# PCB_-_BOARD.net
KiCad netlist of a schematic drawn in EAGLE
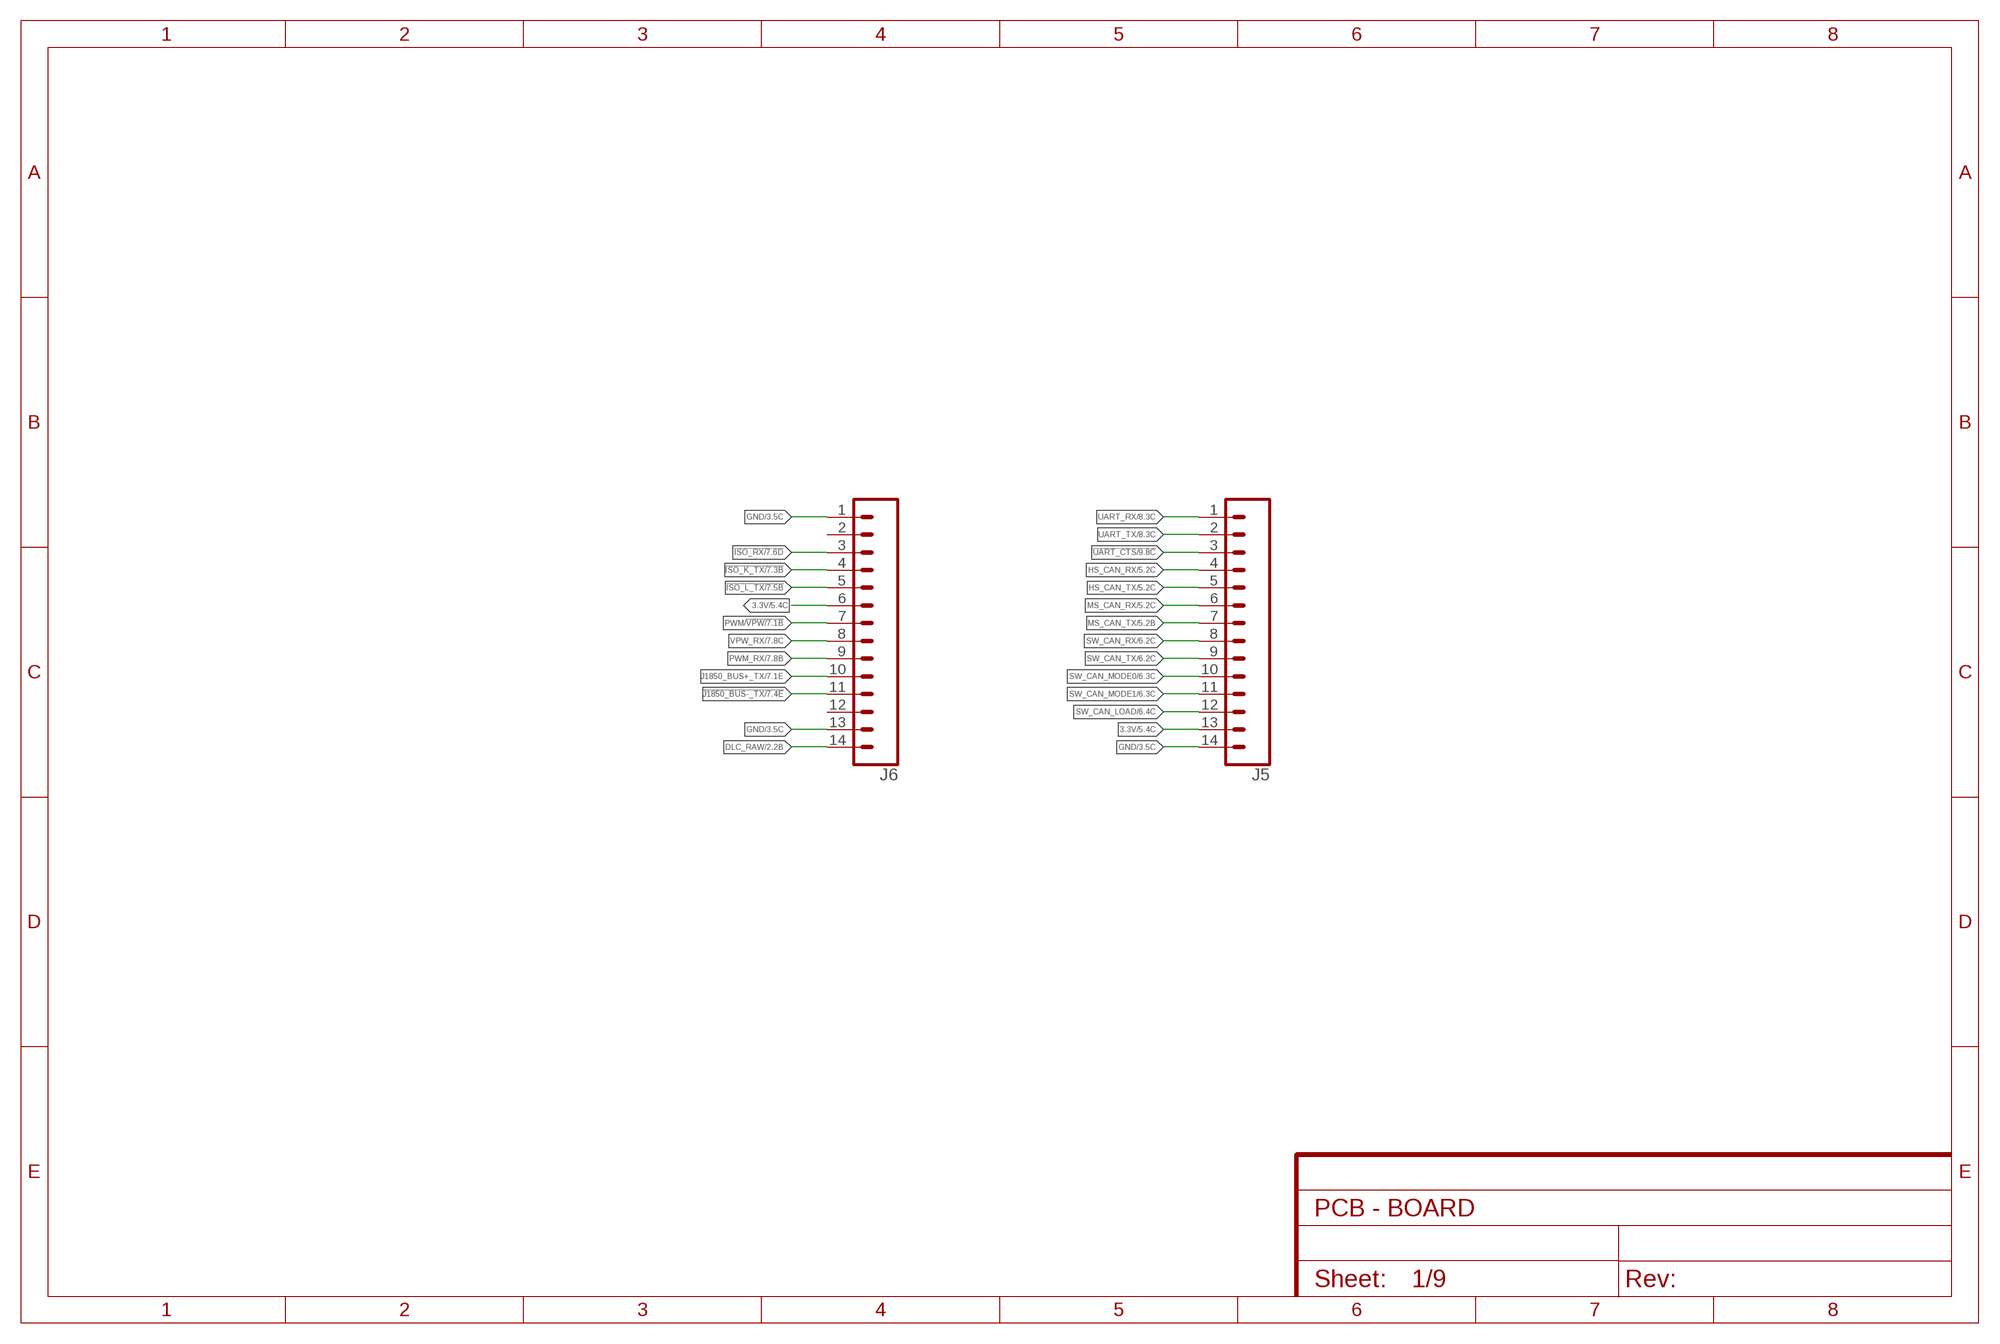
[diagram p0: schematic, sheet 1]
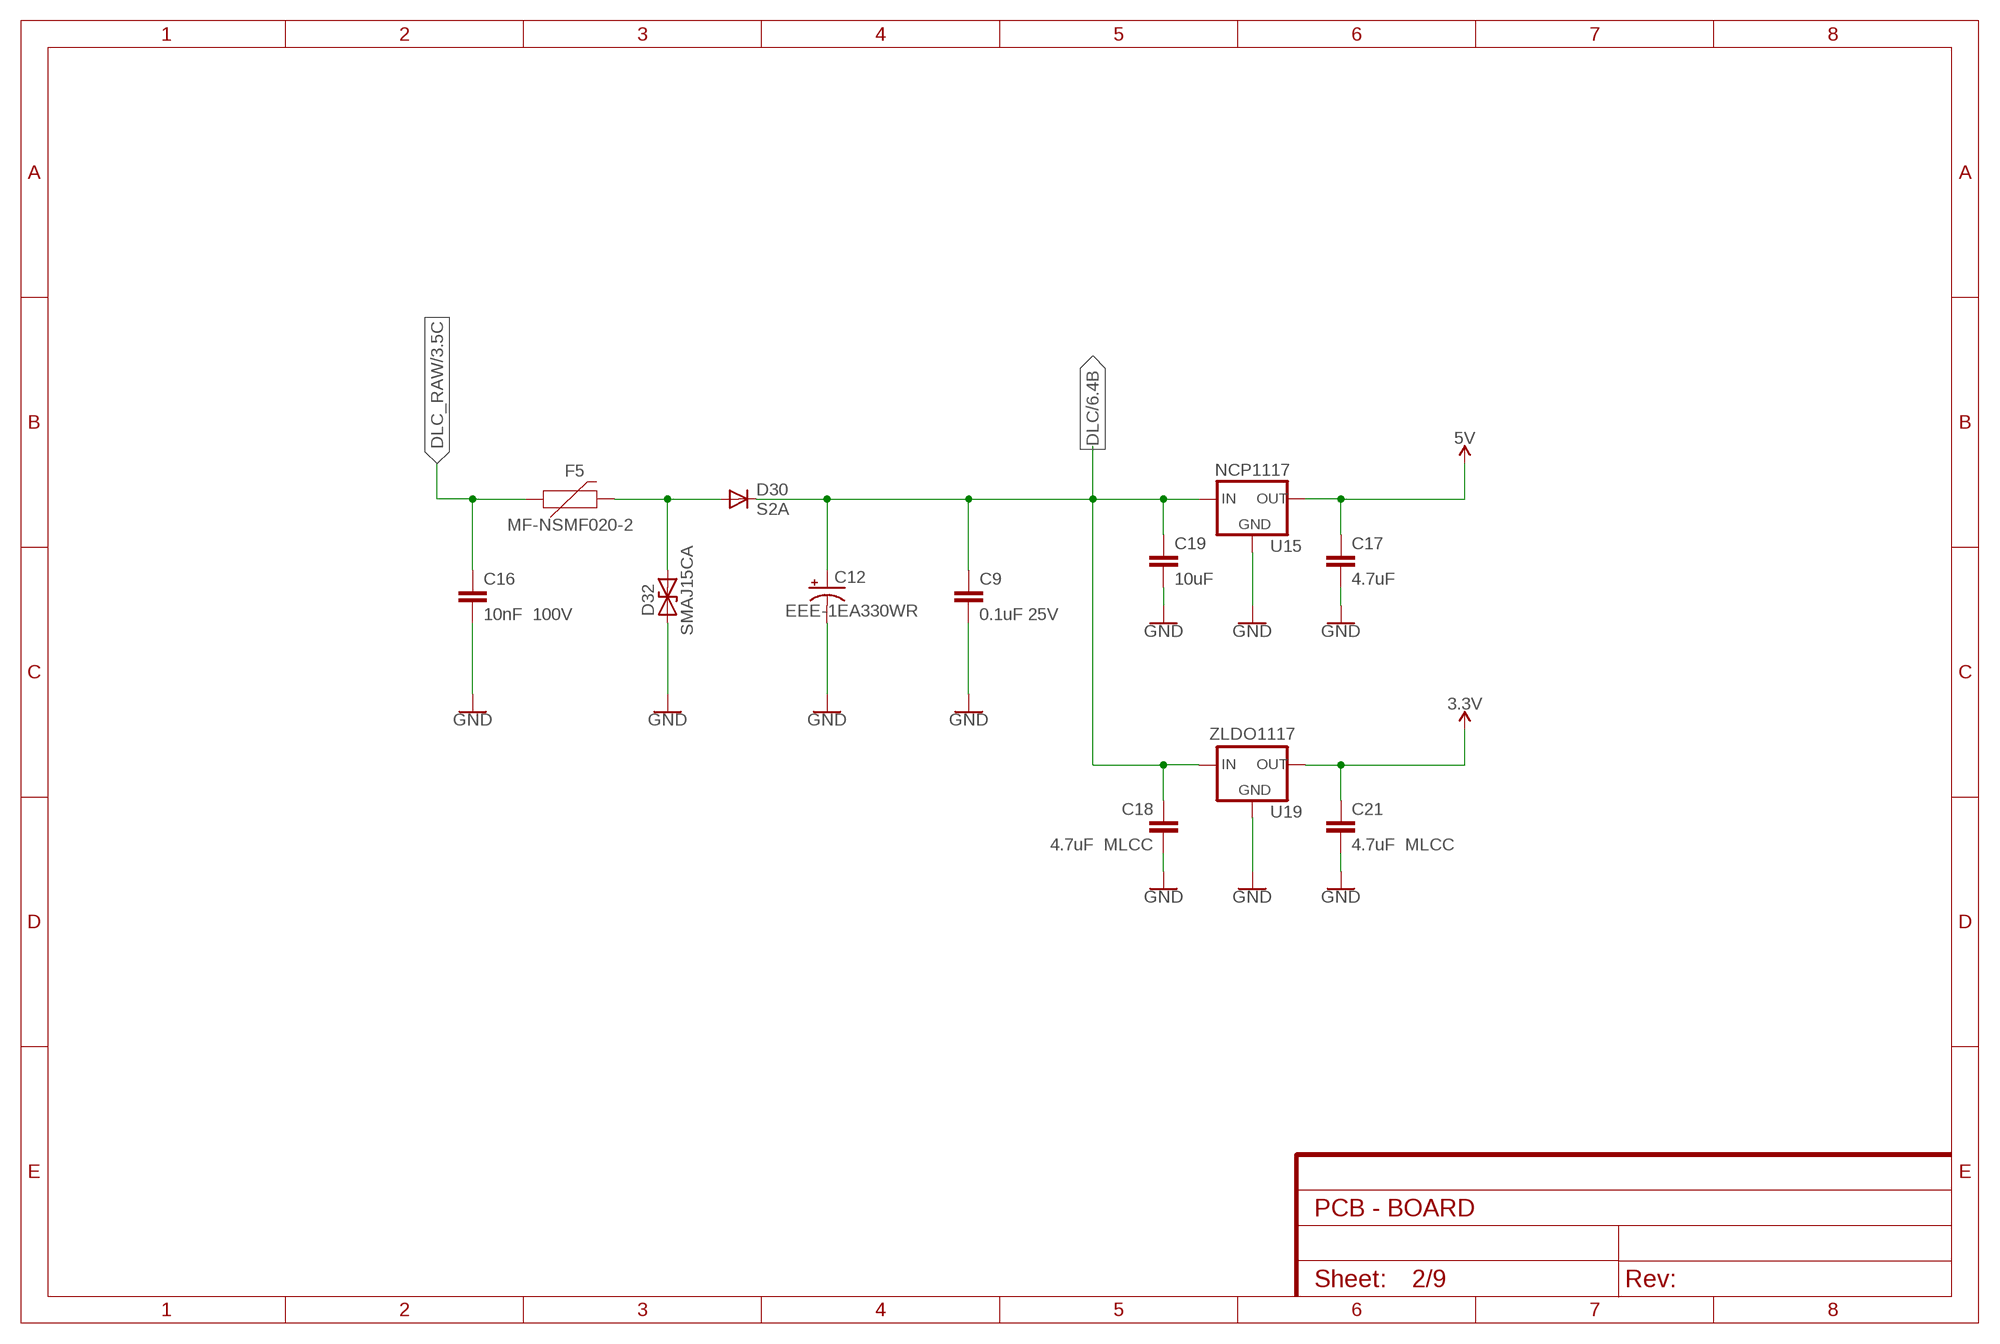
[diagram p1: schematic, sheet 2]
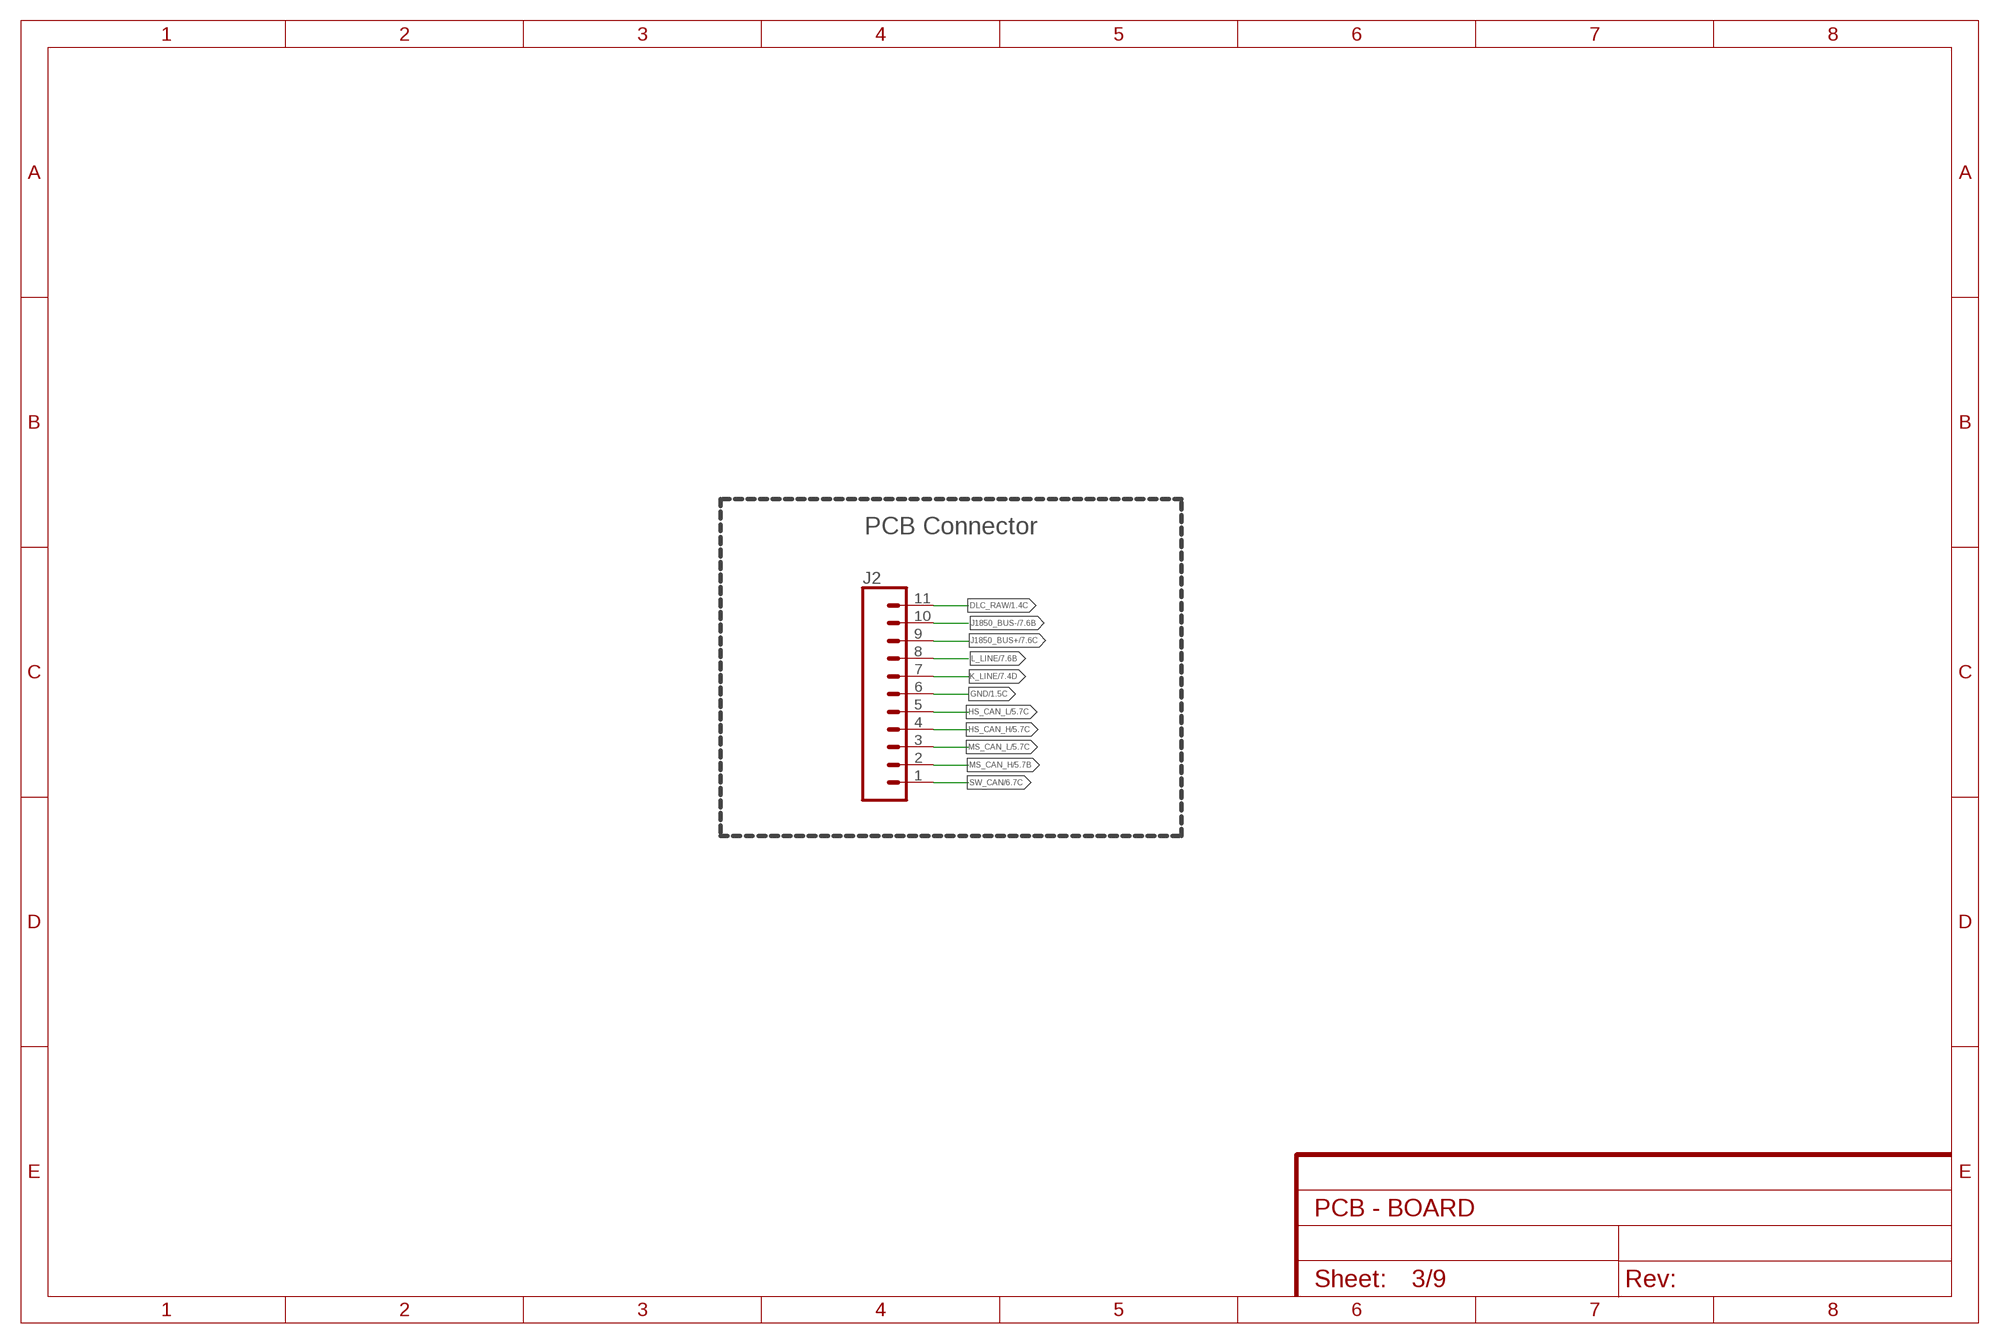
[diagram p2: schematic, sheet 3]
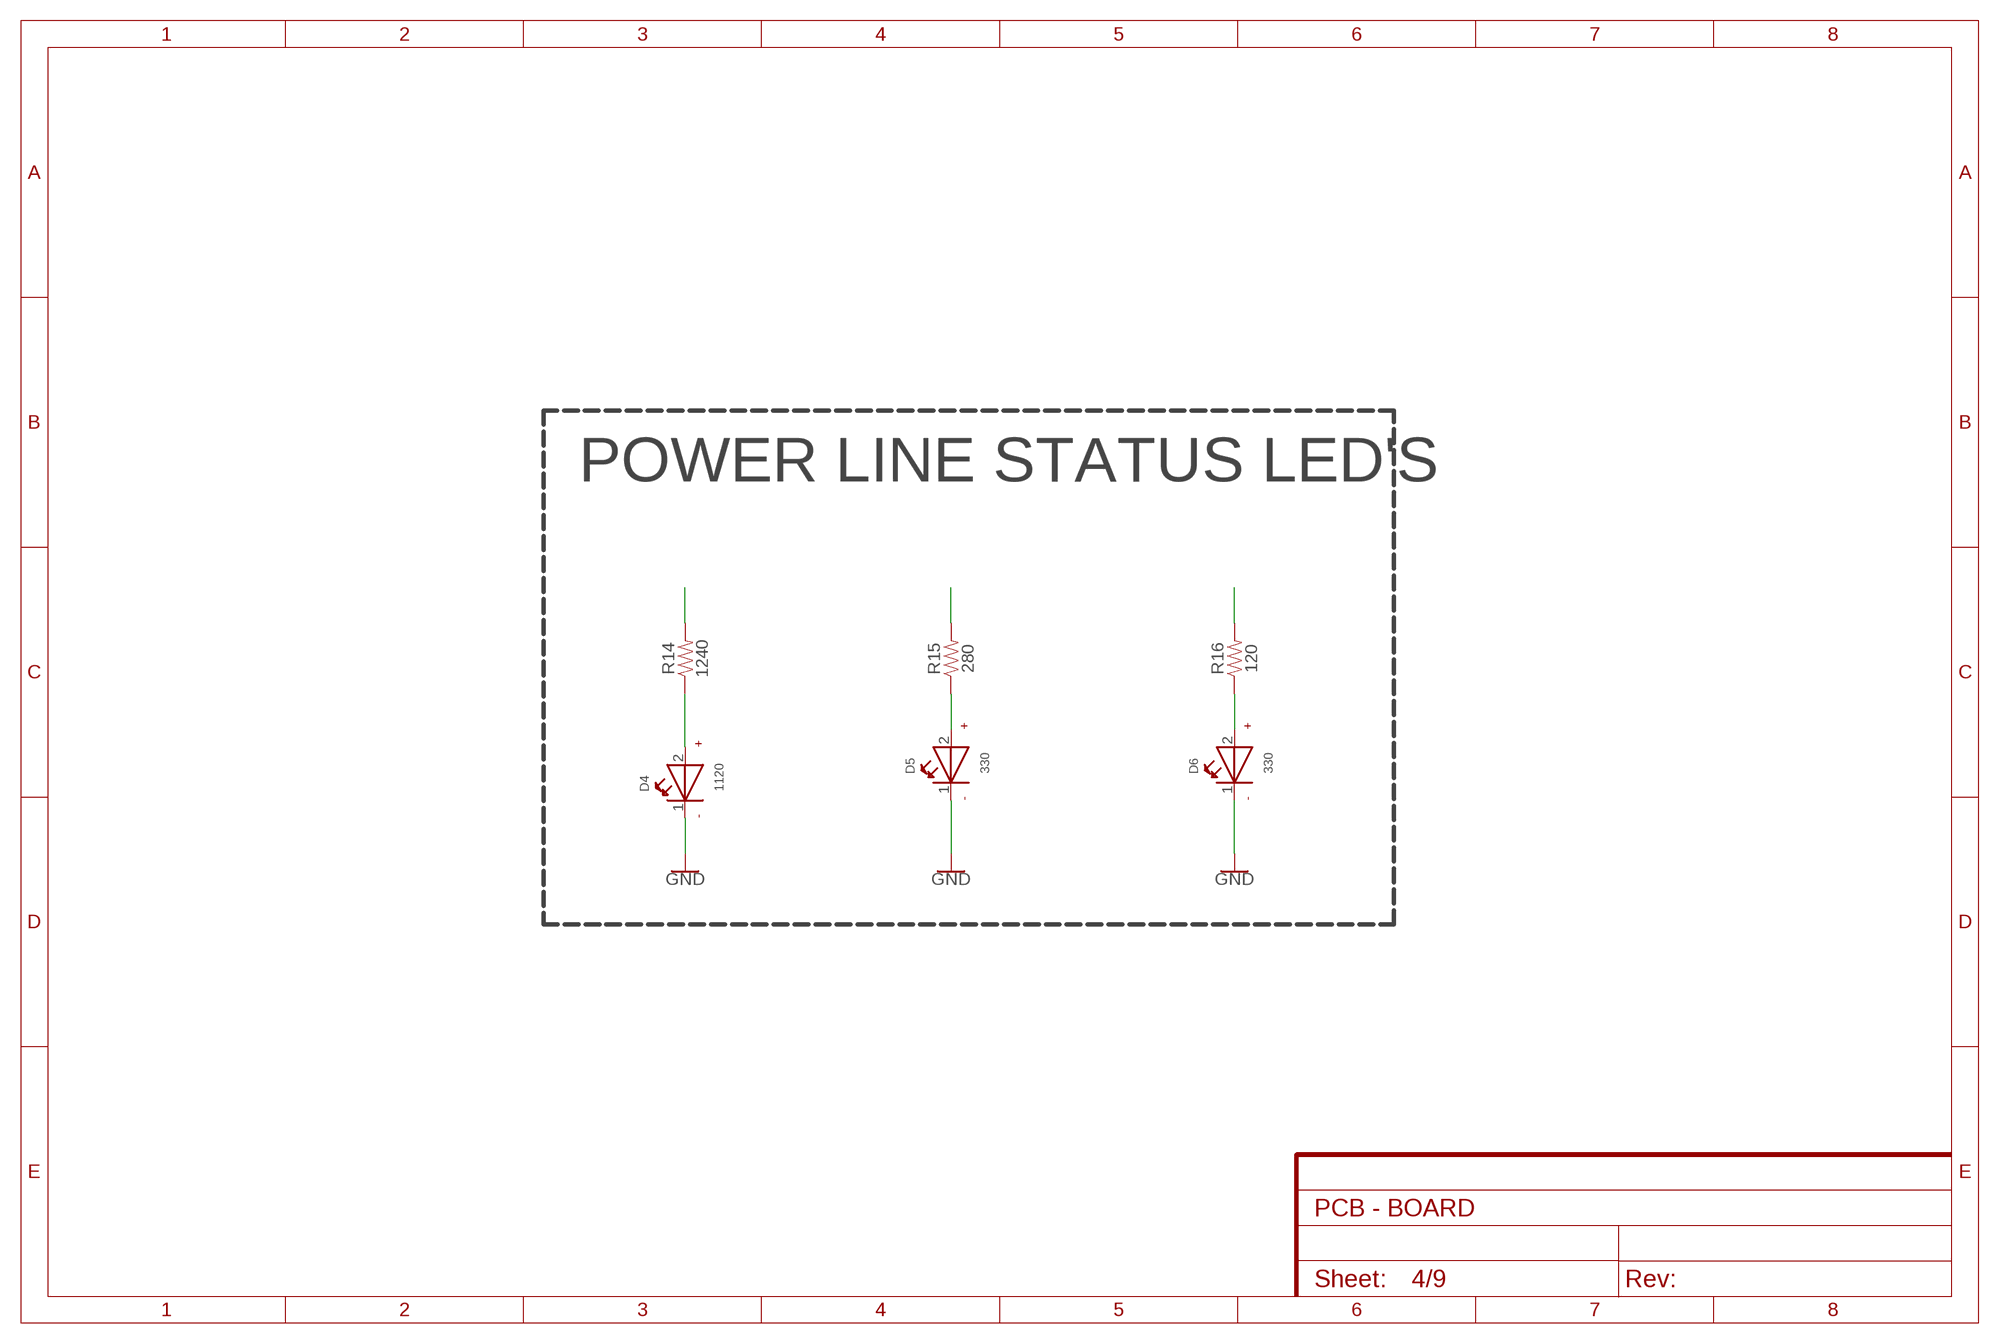
[diagram p3: schematic, sheet 4]
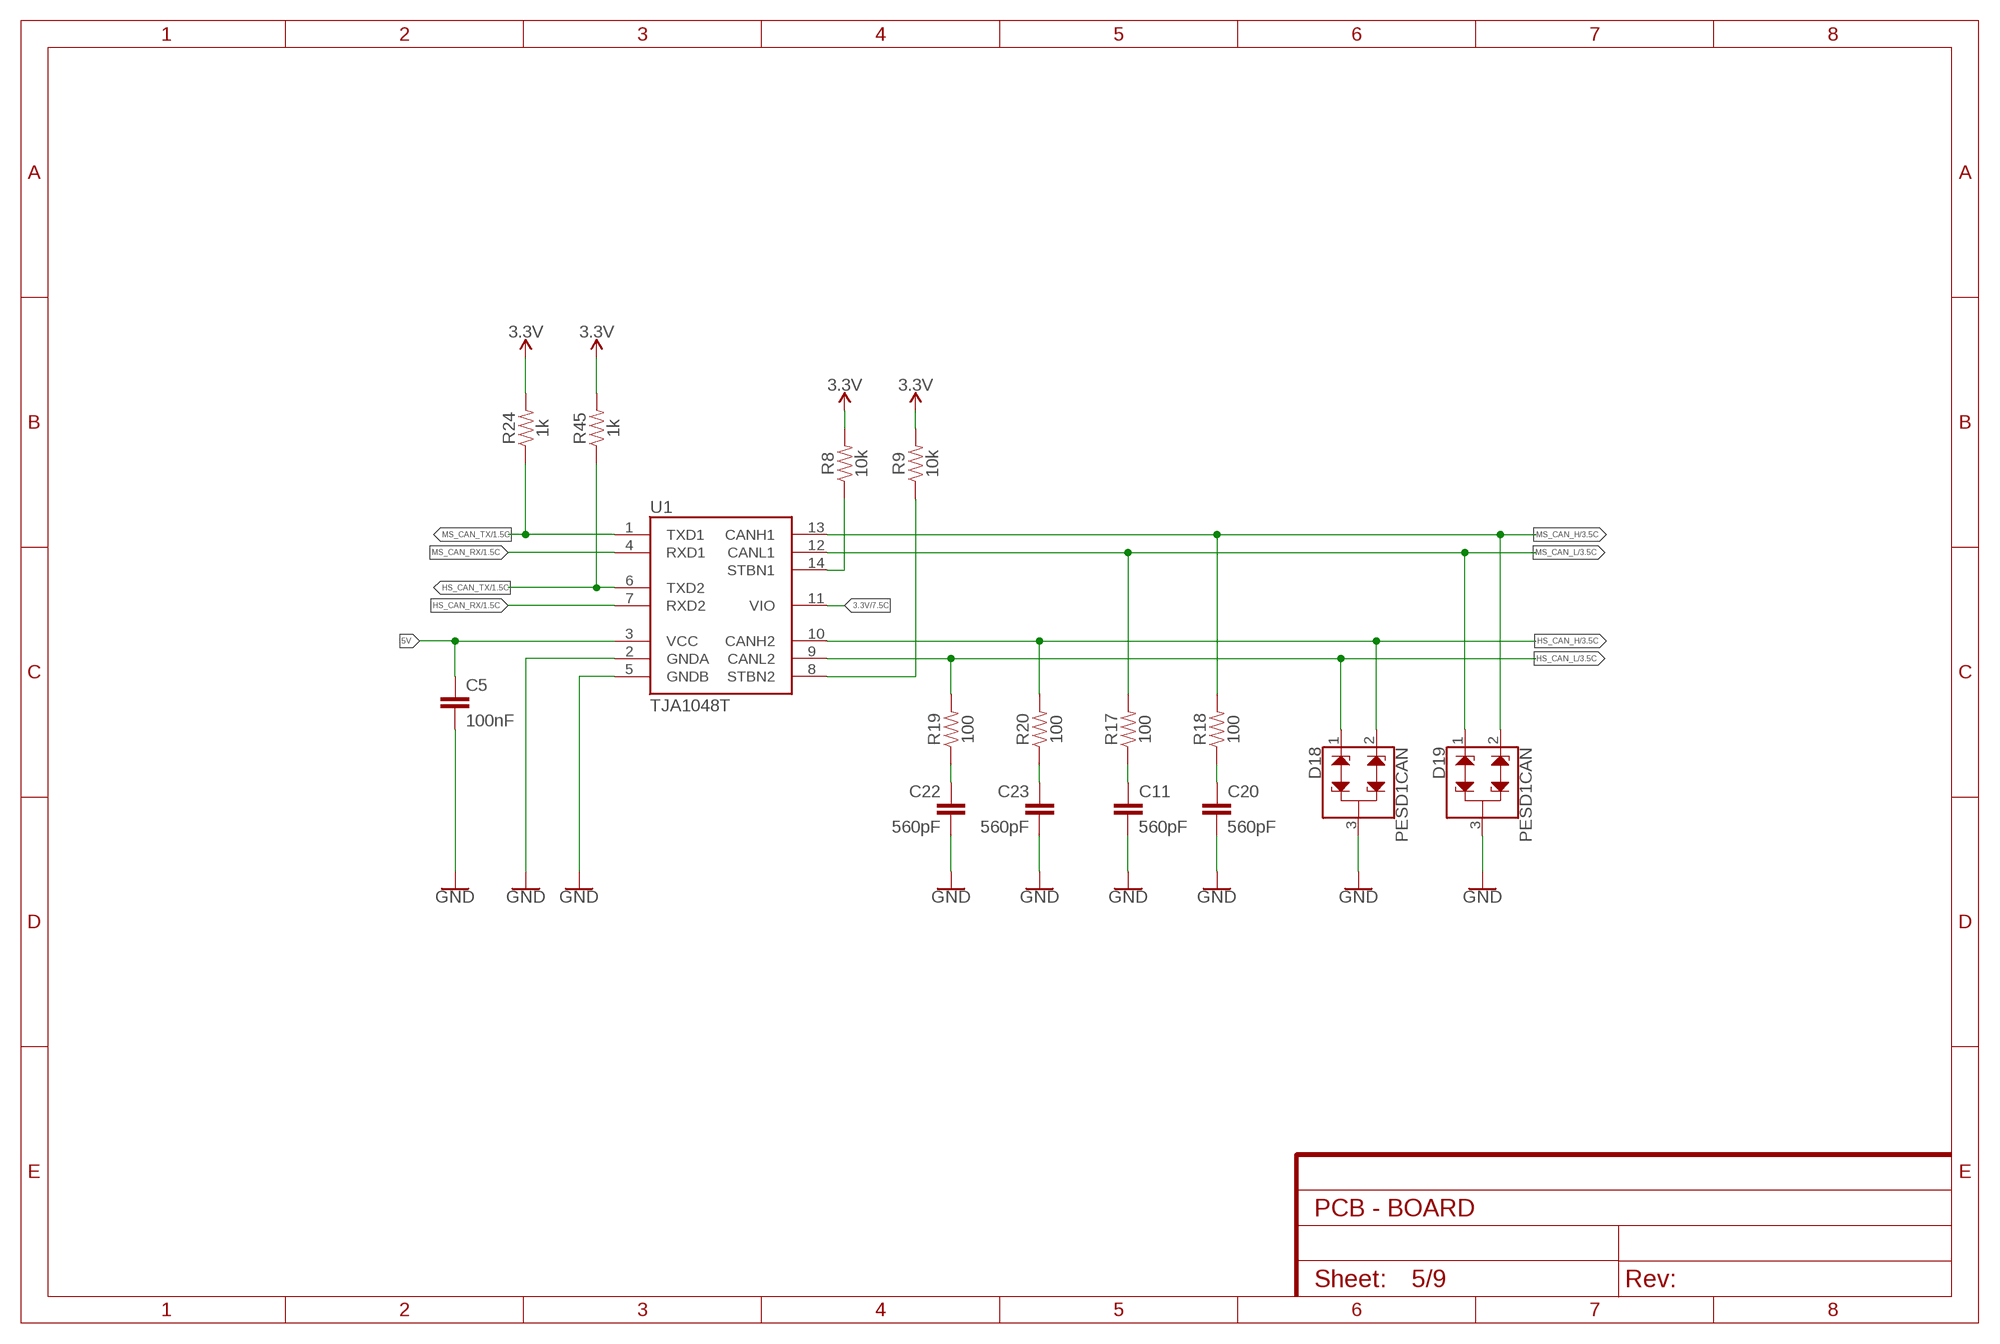
[diagram p4: schematic, sheet 5]
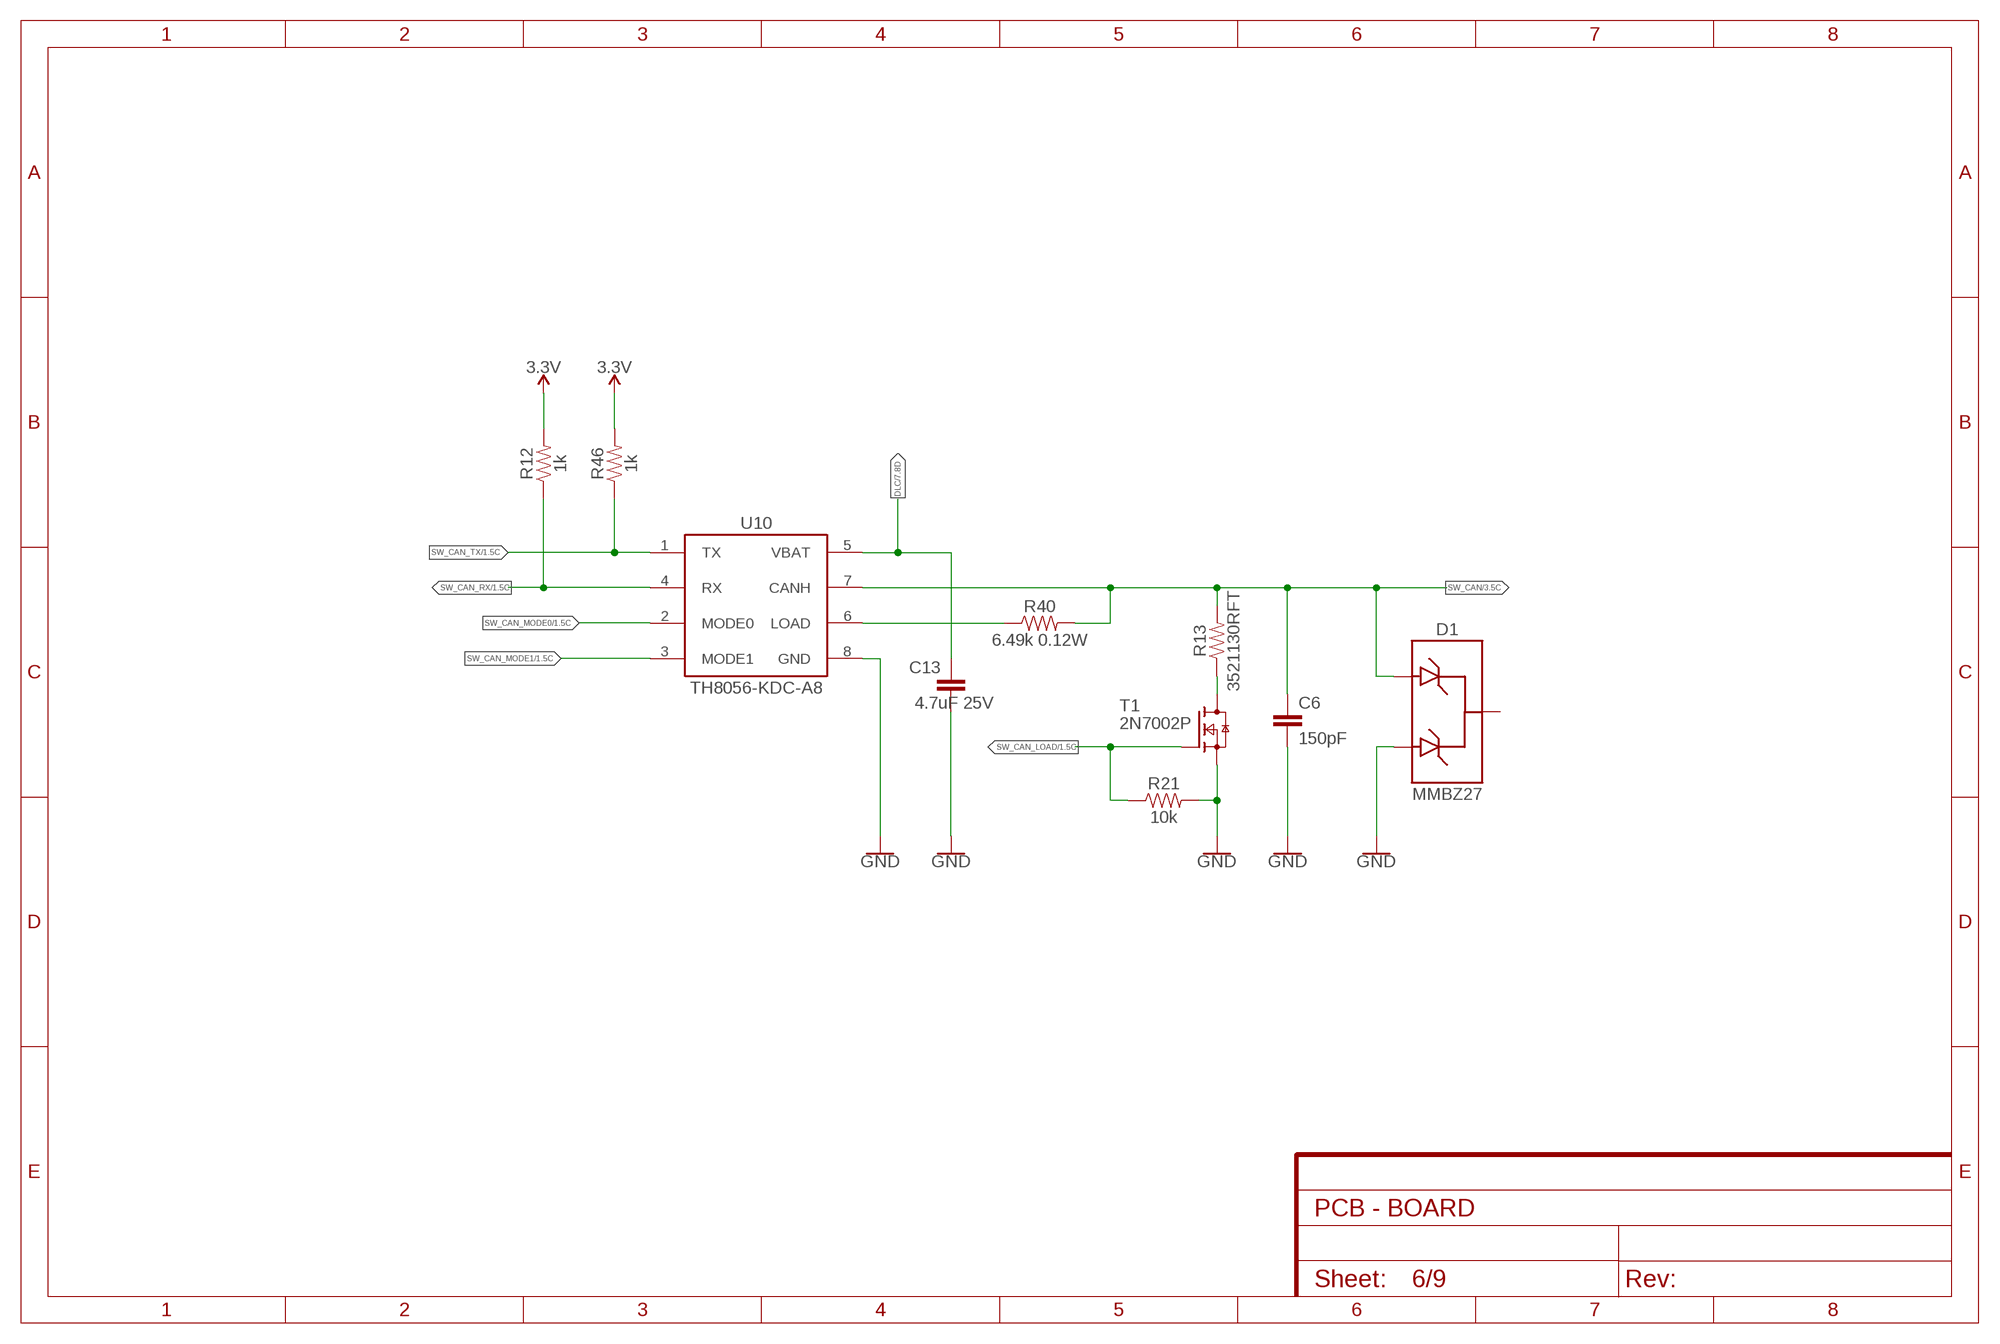
[diagram p5: schematic, sheet 6]
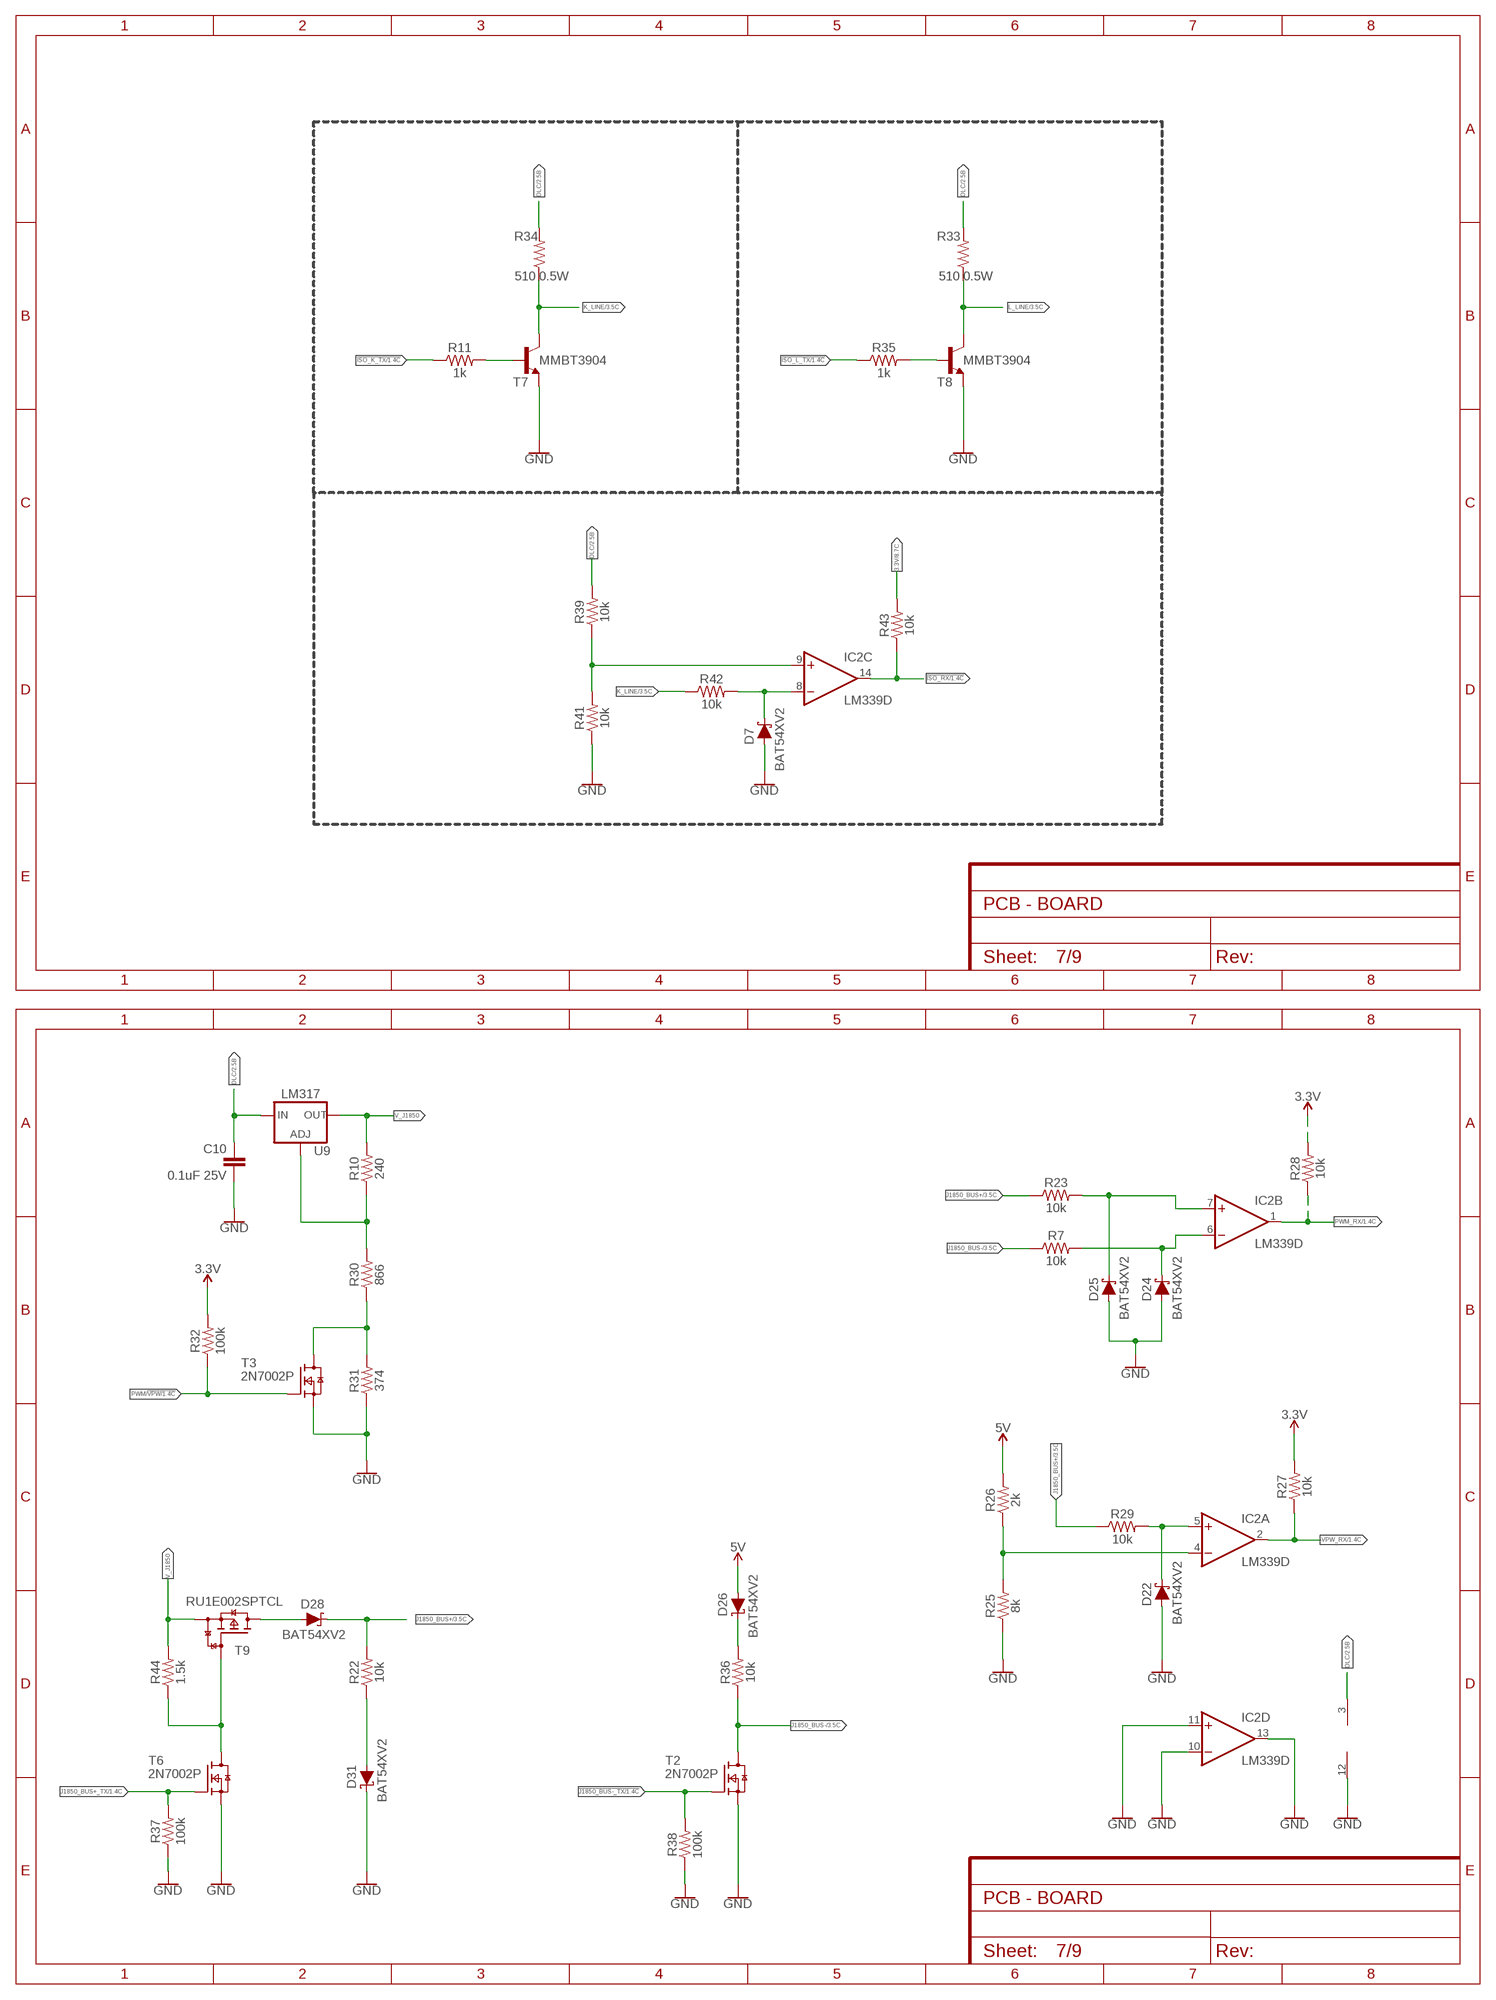
[diagram p6: schematic, sheet 7]
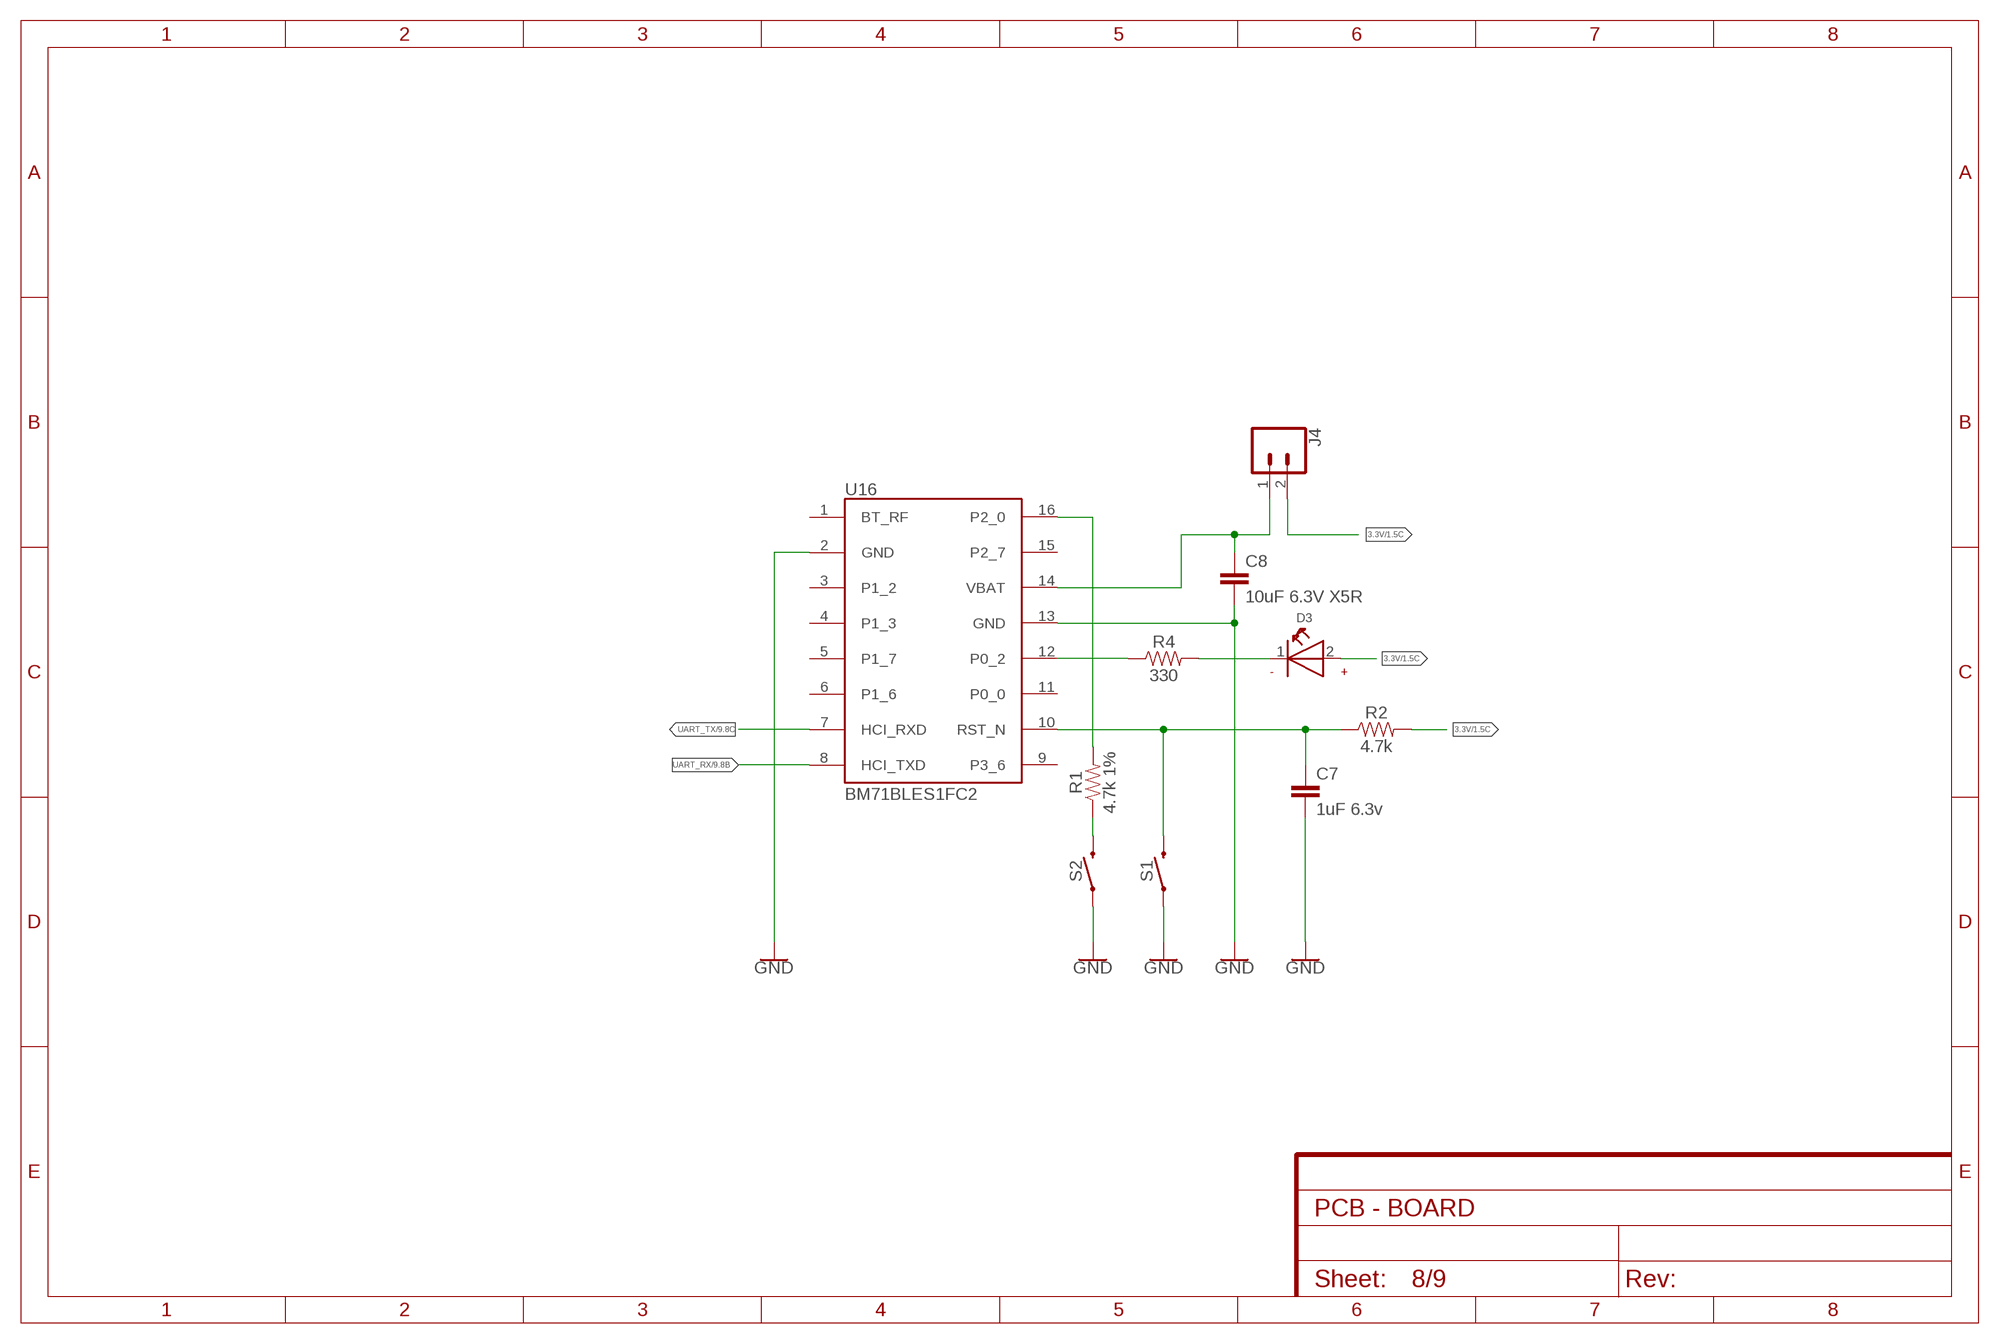
[diagram p7: schematic, sheet 8]
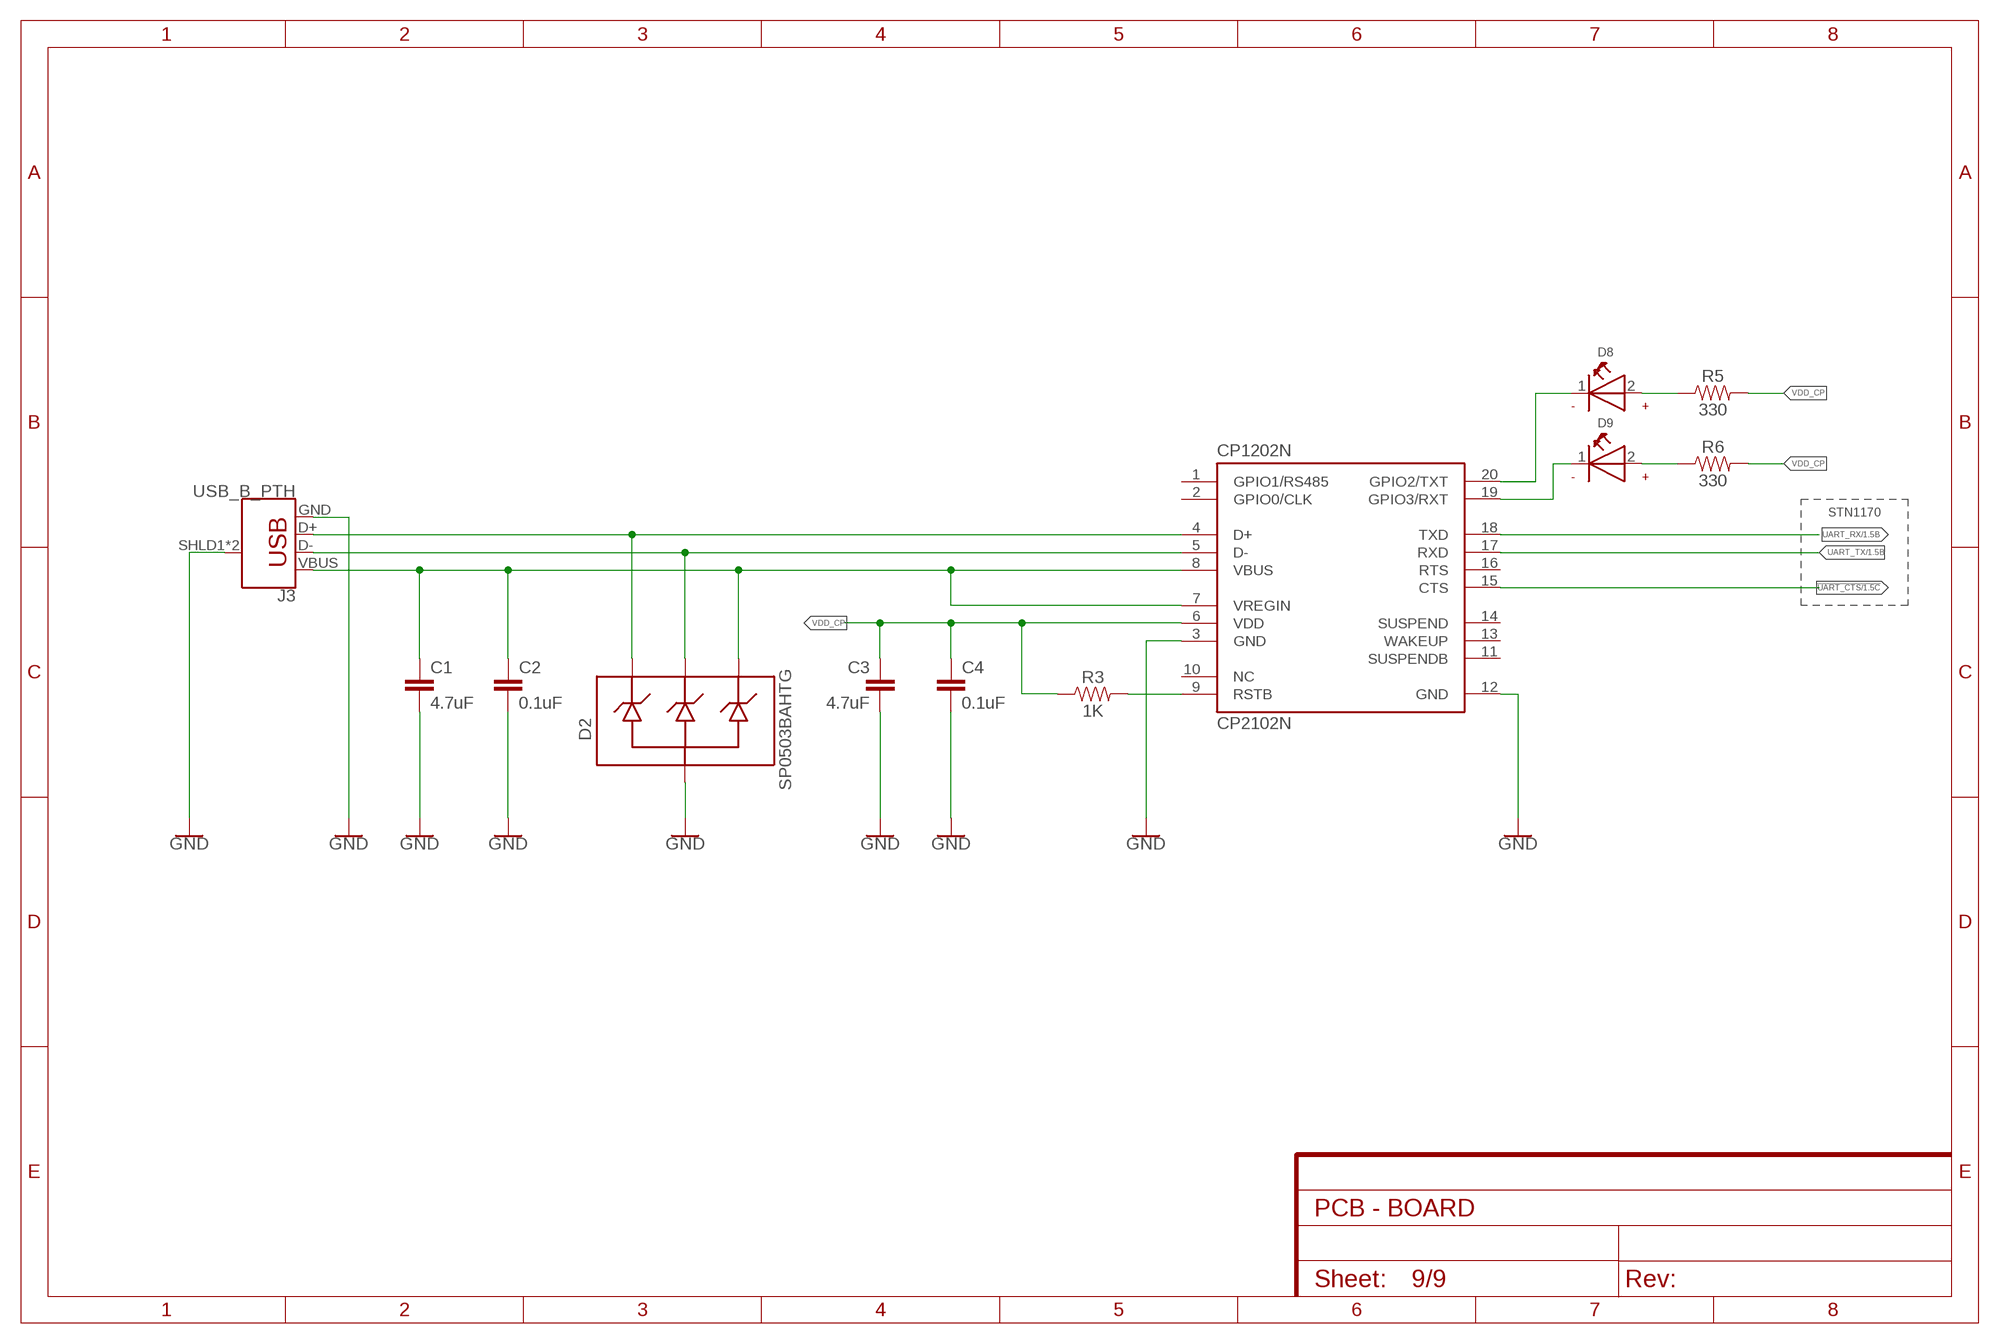
[diagram p8: schematic, sheet 9]

(export (version "E")
  (design (tool "Eeschema 10.0.6"))
  (components
    (comp (ref "D4")
      (value "1120")
      (footprint "eagle-import:WL-SMCW_1206")
      (libsource (lib "eagle-import") (part "WL-SMCW-150120BS75000-B"))
    )
    (comp (ref "D5")
      (value "330")
      (footprint "eagle-import:WL-SMCW_1206")
      (libsource (lib "eagle-import") (part "WL-SMCW-150120BS75000-B"))
    )
    (comp (ref "D6")
      (value "330")
      (footprint "eagle-import:WL-SMCW_1206")
      (libsource (lib "eagle-import") (part "WL-SMCW-150120BS75000-B"))
    )
    (comp (ref "R14")
      (value "1240")
      (footprint "eagle-import:0805")
      (libsource (lib "eagle-import") (part "0.3OHM-0805-1/8W-1%"))
    )
    (comp (ref "R15")
      (value "280")
      (footprint "eagle-import:0805")
      (libsource (lib "eagle-import") (part "0.3OHM-0805-1/8W-1%"))
    )
    (comp (ref "R16")
      (value "120")
      (footprint "eagle-import:0805")
      (libsource (lib "eagle-import") (part "0.3OHM-0805-1/8W-1%"))
    )
    (comp (ref "J5")
      (value "CONN_14")
      (footprint "eagle-import:1X14")
      (libsource (lib "eagle-import") (part "CONN_14"))
    )
    (comp (ref "J6")
      (value "CONN_14")
      (footprint "eagle-import:1X14")
      (libsource (lib "eagle-import") (part "CONN_14"))
    )
    (comp (ref "C7")
      (value "1uF 6.3v")
      (footprint "eagle-import:0805")
      (libsource (lib "eagle-import") (part "1.0UF-0805-25V-(+80/-20%)"))
    )
    (comp (ref "C8")
      (value "10uF 6.3V X5R")
      (footprint "eagle-import:0805")
      (libsource (lib "eagle-import") (part "1.0UF-0805-25V-(+80/-20%)"))
    )
    (comp (ref "D3")
      (value "WL-SMCW-150120BS75000-B")
      (footprint "eagle-import:WL-SMCW_1206")
      (libsource (lib "eagle-import") (part "WL-SMCW-150120BS75000-B"))
    )
    (comp (ref "J4")
      (value "CONN_02")
      (footprint "eagle-import:1X02")
      (libsource (lib "eagle-import") (part "CONN_02"))
    )
    (comp (ref "R1")
      (value "4.7k 1%")
      (footprint "eagle-import:0805")
      (libsource (lib "eagle-import") (part "0.3OHM-0805-1/8W-1%"))
    )
    (comp (ref "R2")
      (value "4.7k")
      (footprint "eagle-import:0805")
      (libsource (lib "eagle-import") (part "0.3OHM-0805-1/8W-1%"))
    )
    (comp (ref "R4")
      (value "330")
      (footprint "eagle-import:0805")
      (libsource (lib "eagle-import") (part "0.3OHM-0805-1/8W-1%"))
    )
    (comp (ref "S1")
      (value "B3U")
      (footprint "eagle-import:B3U-WO-GT-WO-B")
      (libsource (lib "eagle-import") (part "B3U"))
    )
    (comp (ref "S2")
      (value "B3U")
      (footprint "eagle-import:B3U-WO-GT-WO-B")
      (libsource (lib "eagle-import") (part "B3U"))
    )
    (comp (ref "U16")
      (value "BM71BLES1FC2")
      (footprint "eagle-import:RN4871")
      (libsource (lib "eagle-import") (part "BM71BLES1FC2"))
    )
    (comp (ref "J2")
      (value "CONN_11")
      (footprint "eagle-import:1X11")
      (libsource (lib "eagle-import") (part "CONN_11"))
    )
    (comp (ref "C6")
      (value "150pF")
      (footprint "eagle-import:0805")
      (libsource (lib "eagle-import") (part "1.0UF-0805-25V-(+80/-20%)"))
    )
    (comp (ref "C13")
      (value "4.7uF 25V")
      (footprint "eagle-import:0805")
      (libsource (lib "eagle-import") (part "1.0UF-0805-25V-(+80/-20%)"))
    )
    (comp (ref "D1")
      (value "MMBZ27")
      (footprint "eagle-import:SOT23-3")
      (libsource (lib "eagle-import") (part "MMBZ27"))
    )
    (comp (ref "R12")
      (value "1k")
      (footprint "eagle-import:0805")
      (libsource (lib "eagle-import") (part "0.3OHM-0805-1/8W-1%"))
    )
    (comp (ref "R13")
      (value "3521130RFT")
      (footprint "eagle-import:3521")
      (libsource (lib "eagle-import") (part "3521130RFT"))
    )
    (comp (ref "R21")
      (value "10k")
      (footprint "eagle-import:0805")
      (libsource (lib "eagle-import") (part "0.3OHM-0805-1/8W-1%"))
    )
    (comp (ref "R40")
      (value "6.49k 0.12W")
      (footprint "eagle-import:1206")
      (libsource (lib "eagle-import") (part "10OHM-1206-1/4W-1%"))
    )
    (comp (ref "R46")
      (value "1k")
      (footprint "eagle-import:0805")
      (libsource (lib "eagle-import") (part "0.3OHM-0805-1/8W-1%"))
    )
    (comp (ref "T1")
      (value "2N7002P")
      (footprint "eagle-import:SOT23")
      (libsource (lib "eagle-import") (part "2N7002P"))
    )
    (comp (ref "U10")
      (value "TH8056-KDC-A8")
      (footprint "eagle-import:SOIC-8")
      (libsource (lib "eagle-import") (part "TH8056-KDC-A8"))
    )
    (comp (ref "C5")
      (value "100nF")
      (footprint "eagle-import:0805")
      (libsource (lib "eagle-import") (part "1.0UF-0805-25V-(+80/-20%)"))
    )
    (comp (ref "C11")
      (value "560pF")
      (footprint "eagle-import:0805")
      (libsource (lib "eagle-import") (part "1.0UF-0805-25V-(+80/-20%)"))
    )
    (comp (ref "C20")
      (value "560pF")
      (footprint "eagle-import:0805")
      (libsource (lib "eagle-import") (part "1.0UF-0805-25V-(+80/-20%)"))
    )
    (comp (ref "C22")
      (value "560pF")
      (footprint "eagle-import:0805")
      (libsource (lib "eagle-import") (part "1.0UF-0805-25V-(+80/-20%)"))
    )
    (comp (ref "C23")
      (value "560pF")
      (footprint "eagle-import:0805")
      (libsource (lib "eagle-import") (part "1.0UF-0805-25V-(+80/-20%)"))
    )
    (comp (ref "D18")
      (value "PESD1CAN")
      (footprint "eagle-import:SOT23-3")
      (libsource (lib "eagle-import") (part "PESD1CAN"))
    )
    (comp (ref "D19")
      (value "PESD1CAN")
      (footprint "eagle-import:SOT23-3")
      (libsource (lib "eagle-import") (part "PESD1CAN"))
    )
    (comp (ref "R8")
      (value "10k")
      (footprint "eagle-import:0805")
      (libsource (lib "eagle-import") (part "0.3OHM-0805-1/8W-1%"))
    )
    (comp (ref "R9")
      (value "10k")
      (footprint "eagle-import:0805")
      (libsource (lib "eagle-import") (part "0.3OHM-0805-1/8W-1%"))
    )
    (comp (ref "R17")
      (value "100")
      (footprint "eagle-import:0805")
      (libsource (lib "eagle-import") (part "0.3OHM-0805-1/8W-1%"))
    )
    (comp (ref "R18")
      (value "100")
      (footprint "eagle-import:0805")
      (libsource (lib "eagle-import") (part "0.3OHM-0805-1/8W-1%"))
    )
    (comp (ref "R19")
      (value "100")
      (footprint "eagle-import:0805")
      (libsource (lib "eagle-import") (part "0.3OHM-0805-1/8W-1%"))
    )
    (comp (ref "R20")
      (value "100")
      (footprint "eagle-import:0805")
      (libsource (lib "eagle-import") (part "0.3OHM-0805-1/8W-1%"))
    )
    (comp (ref "R24")
      (value "1k")
      (footprint "eagle-import:0805")
      (libsource (lib "eagle-import") (part "0.3OHM-0805-1/8W-1%"))
    )
    (comp (ref "R45")
      (value "1k")
      (footprint "eagle-import:0805")
      (libsource (lib "eagle-import") (part "0.3OHM-0805-1/8W-1%"))
    )
    (comp (ref "U1")
      (value "TJA1048T")
      (footprint "eagle-import:SO14")
      (libsource (lib "eagle-import") (part "TJA1048T"))
    )
    (comp (ref "C9")
      (value "0.1uF 25V")
      (footprint "eagle-import:0805")
      (libsource (lib "eagle-import") (part "1.0UF-0805-25V-(+80/-20%)"))
    )
    (comp (ref "C12")
      (value "EEE-1EA330WR")
      (footprint "eagle-import:PANASONIC-C")
      (libsource (lib "eagle-import") (part "EEE-1EA330WR"))
    )
    (comp (ref "C16")
      (value "10nF 100V")
      (footprint "eagle-import:0805")
      (libsource (lib "eagle-import") (part "1.0UF-0805-25V-(+80/-20%)"))
    )
    (comp (ref "C17")
      (value "4.7uF")
      (footprint "eagle-import:0805")
      (libsource (lib "eagle-import") (part "1.0UF-0805-25V-(+80/-20%)"))
    )
    (comp (ref "C18")
      (value "4.7uF MLCC")
      (footprint "eagle-import:0805")
      (libsource (lib "eagle-import") (part "1.0UF-0805-25V-(+80/-20%)"))
    )
    (comp (ref "C19")
      (value "10uF")
      (footprint "eagle-import:0805")
      (libsource (lib "eagle-import") (part "1.0UF-0805-25V-(+80/-20%)"))
    )
    (comp (ref "C21")
      (value "4.7uF MLCC")
      (footprint "eagle-import:0805")
      (libsource (lib "eagle-import") (part "1.0UF-0805-25V-(+80/-20%)"))
    )
    (comp (ref "D30")
      (value "S2A")
      (footprint "eagle-import:DO214AA")
      (fields (field (name "MF") "Fairchild"))
      (libsource (lib "eagle-import") (part "S2A"))
    )
    (comp (ref "D32")
      (value "SMAJ15CA")
      (footprint "eagle-import:DO214AC")
      (fields (field (name "MF") "Littelfuse"))
      (libsource (lib "eagle-import") (part "SMAJCA15"))
    )
    (comp (ref "F5")
      (value "MF-NSMF020-2")
      (footprint "eagle-import:1206")
      (libsource (lib "eagle-import") (part "PPTC_THREE-QUARTER-AMP"))
    )
    (comp (ref "U15")
      (value "NCP1117")
      (footprint "eagle-import:TO-252")
      (libsource (lib "eagle-import") (part "NCP1117DPAK"))
    )
    (comp (ref "U19")
      (value "ZLDO1117")
      (footprint "eagle-import:SOT223")
      (libsource (lib "eagle-import") (part "ZLODO1117SOT223"))
    )
    (comp (ref "C10")
      (value "0.1uF 25V")
      (footprint "eagle-import:0805")
      (libsource (lib "eagle-import") (part "1.0UF-0805-25V-(+80/-20%)"))
    )
    (comp (ref "D7")
      (value "BAT54XV2")
      (footprint "eagle-import:SOD-523F")
      (libsource (lib "eagle-import") (part "BAT54XV2"))
    )
    (comp (ref "D22")
      (value "BAT54XV2")
      (footprint "eagle-import:SOD-523F")
      (libsource (lib "eagle-import") (part "BAT54XV2"))
    )
    (comp (ref "D24")
      (value "BAT54XV2")
      (footprint "eagle-import:SOD-523F")
      (libsource (lib "eagle-import") (part "BAT54XV2"))
    )
    (comp (ref "D25")
      (value "BAT54XV2")
      (footprint "eagle-import:SOD-523F")
      (libsource (lib "eagle-import") (part "BAT54XV2"))
    )
    (comp (ref "D26")
      (value "BAT54XV2")
      (footprint "eagle-import:SOD-523F")
      (libsource (lib "eagle-import") (part "BAT54XV2"))
    )
    (comp (ref "D28")
      (value "BAT54XV2")
      (footprint "eagle-import:SOD-523F")
      (libsource (lib "eagle-import") (part "BAT54XV2"))
    )
    (comp (ref "D31")
      (value "BAT54XV2")
      (footprint "eagle-import:SOD-523F")
      (libsource (lib "eagle-import") (part "BAT54XV2"))
    )
    (comp (ref "IC2")
      (value "LM339D")
      (footprint "eagle-import:SO14")
      (libsource (lib "eagle-import") (part "LM339D"))
    )
    (comp (ref "R7")
      (value "10k")
      (footprint "eagle-import:0805")
      (libsource (lib "eagle-import") (part "0.3OHM-0805-1/8W-1%"))
    )
    (comp (ref "R10")
      (value "240")
      (footprint "eagle-import:0805")
      (libsource (lib "eagle-import") (part "0.3OHM-0805-1/8W-1%"))
    )
    (comp (ref "R11")
      (value "1k")
      (footprint "eagle-import:0805")
      (libsource (lib "eagle-import") (part "0.3OHM-0805-1/8W-1%"))
    )
    (comp (ref "R22")
      (value "10k")
      (footprint "eagle-import:0805")
      (libsource (lib "eagle-import") (part "0.3OHM-0805-1/8W-1%"))
    )
    (comp (ref "R23")
      (value "10k")
      (footprint "eagle-import:0805")
      (libsource (lib "eagle-import") (part "0.3OHM-0805-1/8W-1%"))
    )
    (comp (ref "R25")
      (value "8k")
      (footprint "eagle-import:0805")
      (libsource (lib "eagle-import") (part "0.3OHM-0805-1/8W-1%"))
    )
    (comp (ref "R26")
      (value "2k")
      (footprint "eagle-import:0805")
      (libsource (lib "eagle-import") (part "0.3OHM-0805-1/8W-1%"))
    )
    (comp (ref "R27")
      (value "10k")
      (footprint "eagle-import:0805")
      (libsource (lib "eagle-import") (part "0.3OHM-0805-1/8W-1%"))
    )
    (comp (ref "R28")
      (value "10k")
      (footprint "eagle-import:0805")
      (libsource (lib "eagle-import") (part "0.3OHM-0805-1/8W-1%"))
    )
    (comp (ref "R29")
      (value "10k")
      (footprint "eagle-import:0805")
      (libsource (lib "eagle-import") (part "0.3OHM-0805-1/8W-1%"))
    )
    (comp (ref "R30")
      (value "866")
      (footprint "eagle-import:0805")
      (libsource (lib "eagle-import") (part "0.3OHM-0805-1/8W-1%"))
    )
    (comp (ref "R31")
      (value "374")
      (footprint "eagle-import:0805")
      (libsource (lib "eagle-import") (part "0.3OHM-0805-1/8W-1%"))
    )
    (comp (ref "R32")
      (value "100k")
      (footprint "eagle-import:0805")
      (libsource (lib "eagle-import") (part "0.3OHM-0805-1/8W-1%"))
    )
    (comp (ref "R33")
      (value "510 0.5W")
      (footprint "eagle-import:1210")
      (libsource (lib "eagle-import") (part "0.1OHM-1210-1/2W-1%"))
    )
    (comp (ref "R34")
      (value "510 0.5W")
      (footprint "eagle-import:1210")
      (libsource (lib "eagle-import") (part "0.1OHM-1210-1/2W-1%"))
    )
    (comp (ref "R35")
      (value "1k")
      (footprint "eagle-import:0805")
      (libsource (lib "eagle-import") (part "0.3OHM-0805-1/8W-1%"))
    )
    (comp (ref "R36")
      (value "10k")
      (footprint "eagle-import:0805")
      (libsource (lib "eagle-import") (part "0.3OHM-0805-1/8W-1%"))
    )
    (comp (ref "R37")
      (value "100k")
      (footprint "eagle-import:0805")
      (libsource (lib "eagle-import") (part "0.3OHM-0805-1/8W-1%"))
    )
    (comp (ref "R38")
      (value "100k")
      (footprint "eagle-import:0805")
      (libsource (lib "eagle-import") (part "0.3OHM-0805-1/8W-1%"))
    )
    (comp (ref "R39")
      (value "10k")
      (footprint "eagle-import:0805")
      (libsource (lib "eagle-import") (part "0.3OHM-0805-1/8W-1%"))
    )
    (comp (ref "R41")
      (value "10k")
      (footprint "eagle-import:0805")
      (libsource (lib "eagle-import") (part "0.3OHM-0805-1/8W-1%"))
    )
    (comp (ref "R42")
      (value "10k")
      (footprint "eagle-import:0805")
      (libsource (lib "eagle-import") (part "0.3OHM-0805-1/8W-1%"))
    )
    (comp (ref "R43")
      (value "10k")
      (footprint "eagle-import:0805")
      (libsource (lib "eagle-import") (part "0.3OHM-0805-1/8W-1%"))
    )
    (comp (ref "R44")
      (value "1.5k")
      (footprint "eagle-import:0805")
      (libsource (lib "eagle-import") (part "0.3OHM-0805-1/8W-1%"))
    )
    (comp (ref "T2")
      (value "2N7002P")
      (footprint "eagle-import:SOT23")
      (libsource (lib "eagle-import") (part "2N7002P"))
    )
    (comp (ref "T3")
      (value "2N7002P")
      (footprint "eagle-import:SOT23")
      (libsource (lib "eagle-import") (part "2N7002P"))
    )
    (comp (ref "T6")
      (value "2N7002P")
      (footprint "eagle-import:SOT23")
      (libsource (lib "eagle-import") (part "2N7002P"))
    )
    (comp (ref "T7")
      (value "MMBT3904")
      (footprint "eagle-import:SOT23-BEC")
      (libsource (lib "eagle-import") (part "-NPN-SOT23-BECMMBT3904LT1"))
    )
    (comp (ref "T8")
      (value "MMBT3904")
      (footprint "eagle-import:SOT23-BEC")
      (libsource (lib "eagle-import") (part "-NPN-SOT23-BECMMBT3904LT1"))
    )
    (comp (ref "T9")
      (value "RU1E002SPTCL")
      (footprint "eagle-import:SOT323")
      (libsource (lib "eagle-import") (part "BSS84AKW"))
    )
    (comp (ref "U9")
      (value "LM317")
      (footprint "eagle-import:SOT223")
      (libsource (lib "eagle-import") (part "V_REG_317SMD"))
    )
    (comp (ref "C1")
      (value "4.7uF")
      (footprint "eagle-import:0805")
      (libsource (lib "eagle-import") (part "1.0UF-0805-25V-(+80/-20%)"))
    )
    (comp (ref "C2")
      (value "0.1uF")
      (footprint "eagle-import:0805")
      (libsource (lib "eagle-import") (part "1.0UF-0805-25V-(+80/-20%)"))
    )
    (comp (ref "C3")
      (value "4.7uF")
      (footprint "eagle-import:0805")
      (libsource (lib "eagle-import") (part "1.0UF-0805-25V-(+80/-20%)"))
    )
    (comp (ref "C4")
      (value "0.1uF")
      (footprint "eagle-import:0805")
      (libsource (lib "eagle-import") (part "1.0UF-0805-25V-(+80/-20%)"))
    )
    (comp (ref "CP1202N")
      (value "CP2102N")
      (footprint "eagle-import:QFN20")
      (libsource (lib "eagle-import") (part "CP2102N"))
    )
    (comp (ref "D2")
      (value "SP0503BAHTG")
      (footprint "eagle-import:SOT143-4")
      (libsource (lib "eagle-import") (part "SP0503BAHTG"))
    )
    (comp (ref "D8")
      (value "WL-SMCW-150120BS75000-B")
      (footprint "eagle-import:WL-SMCW_1206")
      (libsource (lib "eagle-import") (part "WL-SMCW-150120BS75000-B"))
    )
    (comp (ref "D9")
      (value "WL-SMCW-150120BS75000-B")
      (footprint "eagle-import:WL-SMCW_1206")
      (libsource (lib "eagle-import") (part "WL-SMCW-150120BS75000-B"))
    )
    (comp (ref "J3")
      (value "USB_B_PTH")
      (footprint "eagle-import:USB-B-PTH")
      (libsource (lib "eagle-import") (part "USB_B_PTH"))
    )
    (comp (ref "R3")
      (value "1K")
      (footprint "eagle-import:0805")
      (libsource (lib "eagle-import") (part "0.3OHM-0805-1/8W-1%"))
    )
    (comp (ref "R5")
      (value "330")
      (footprint "eagle-import:0805")
      (libsource (lib "eagle-import") (part "0.3OHM-0805-1/8W-1%"))
    )
    (comp (ref "R6")
      (value "330")
      (footprint "eagle-import:0805")
      (libsource (lib "eagle-import") (part "0.3OHM-0805-1/8W-1%"))
    )
  )
  (nets
    (net (code "1") (name "3.3V") (class "Default")
      (node (ref "C21") (pin "1") (pinfunction "1_1") (pintype "passive"))
      (node (ref "C8") (pin "1") (pinfunction "1_1") (pintype "passive"))
      (node (ref "D3") (pin "2") (pinfunction "+_2") (pintype "passive"))
      (node (ref "J4") (pin "1") (pinfunction "1_1") (pintype "passive"))
      (node (ref "J4") (pin "2") (pinfunction "2_2") (pintype "passive"))
      (node (ref "J5") (pin "13") (pinfunction "13_13") (pintype "passive"))
      (node (ref "J6") (pin "6") (pinfunction "6_6") (pintype "passive"))
      (node (ref "R12") (pin "2") (pinfunction "2_2") (pintype "passive"))
      (node (ref "R16") (pin "2") (pinfunction "2_2") (pintype "passive"))
      (node (ref "R2") (pin "2") (pinfunction "2_2") (pintype "passive"))
      (node (ref "R24") (pin "2") (pinfunction "2_2") (pintype "passive"))
      (node (ref "R27") (pin "2") (pinfunction "2_2") (pintype "passive"))
      (node (ref "R28") (pin "2") (pinfunction "2_2") (pintype "passive"))
      (node (ref "R32") (pin "2") (pinfunction "2_2") (pintype "passive"))
      (node (ref "R43") (pin "2") (pinfunction "2_2") (pintype "passive"))
      (node (ref "R45") (pin "2") (pinfunction "2_2") (pintype "passive"))
      (node (ref "R46") (pin "2") (pinfunction "2_2") (pintype "passive"))
      (node (ref "R8") (pin "2") (pinfunction "2_2") (pintype "passive"))
      (node (ref "R9") (pin "2") (pinfunction "2_2") (pintype "passive"))
      (node (ref "U1") (pin "11") (pinfunction "VIO_11") (pintype "power_in"))
      (node (ref "U16") (pin "14") (pinfunction "VBAT_14") (pintype "power_in"))
      (node (ref "U19") (pin "2") (pinfunction "OUT_2") (pintype "passive"))
      (node (ref "U19") (pin "4") (pinfunction "OUT_4") (pintype "passive"))
    )
    (net (code "2") (name "5V") (class "Default")
      (node (ref "C17") (pin "1") (pinfunction "1_1") (pintype "passive"))
      (node (ref "C5") (pin "1") (pinfunction "1_1") (pintype "passive"))
      (node (ref "D26") (pin "A") (pinfunction "A_A") (pintype "passive"))
      (node (ref "R15") (pin "2") (pinfunction "2_2") (pintype "passive"))
      (node (ref "R26") (pin "2") (pinfunction "2_2") (pintype "passive"))
      (node (ref "U1") (pin "3") (pinfunction "VCC_3") (pintype "power_in"))
      (node (ref "U15") (pin "2") (pinfunction "OUT_2") (pintype "passive"))
    )
    (net (code "3") (name "DLC") (class "Default")
      (node (ref "C10") (pin "1") (pinfunction "1_1") (pintype "passive"))
      (node (ref "C12") (pin "2") (pinfunction "+_2") (pintype "passive"))
      (node (ref "C13") (pin "1") (pinfunction "1_1") (pintype "passive"))
      (node (ref "C18") (pin "1") (pinfunction "1_1") (pintype "passive"))
      (node (ref "C19") (pin "1") (pinfunction "1_1") (pintype "passive"))
      (node (ref "C9") (pin "1") (pinfunction "1_1") (pintype "passive"))
      (node (ref "D30") (pin "C") (pinfunction "C_C") (pintype "passive"))
      (node (ref "IC2") (pin "3") (pinfunction "V+_3") (pintype "power_in"))
      (node (ref "R14") (pin "2") (pinfunction "2_2") (pintype "passive"))
      (node (ref "R33") (pin "2") (pinfunction "2_2") (pintype "passive"))
      (node (ref "R34") (pin "2") (pinfunction "2_2") (pintype "passive"))
      (node (ref "R39") (pin "2") (pinfunction "2_2") (pintype "passive"))
      (node (ref "U10") (pin "5") (pinfunction "VBAT_5") (pintype "power_in"))
      (node (ref "U15") (pin "3") (pinfunction "IN_3") (pintype "input"))
      (node (ref "U19") (pin "3") (pinfunction "IN_3") (pintype "input"))
      (node (ref "U9") (pin "3") (pinfunction "IN_3") (pintype "input"))
    )
    (net (code "4") (name "DLC_RAW") (class "Default")
      (node (ref "C16") (pin "1") (pinfunction "1_1") (pintype "passive"))
      (node (ref "F5") (pin "1") (pinfunction "1_1") (pintype "bidirectional"))
      (node (ref "J2") (pin "11") (pinfunction "11_11") (pintype "passive"))
      (node (ref "J6") (pin "14") (pinfunction "14_14") (pintype "passive"))
    )
    (net (code "5") (name "GND") (class "Default")
      (node (ref "C1") (pin "2") (pinfunction "2_2") (pintype "passive"))
      (node (ref "C10") (pin "2") (pinfunction "2_2") (pintype "passive"))
      (node (ref "C11") (pin "2") (pinfunction "2_2") (pintype "passive"))
      (node (ref "C12") (pin "1") (pinfunction "-_1") (pintype "passive"))
      (node (ref "C13") (pin "2") (pinfunction "2_2") (pintype "passive"))
      (node (ref "C16") (pin "2") (pinfunction "2_2") (pintype "passive"))
      (node (ref "C17") (pin "2") (pinfunction "2_2") (pintype "passive"))
      (node (ref "C18") (pin "2") (pinfunction "2_2") (pintype "passive"))
      (node (ref "C19") (pin "2") (pinfunction "2_2") (pintype "passive"))
      (node (ref "C2") (pin "2") (pinfunction "2_2") (pintype "passive"))
      (node (ref "C20") (pin "2") (pinfunction "2_2") (pintype "passive"))
      (node (ref "C21") (pin "2") (pinfunction "2_2") (pintype "passive"))
      (node (ref "C22") (pin "2") (pinfunction "2_2") (pintype "passive"))
      (node (ref "C23") (pin "2") (pinfunction "2_2") (pintype "passive"))
      (node (ref "C3") (pin "2") (pinfunction "2_2") (pintype "passive"))
      (node (ref "C4") (pin "2") (pinfunction "2_2") (pintype "passive"))
      (node (ref "C5") (pin "2") (pinfunction "2_2") (pintype "passive"))
      (node (ref "C6") (pin "2") (pinfunction "2_2") (pintype "passive"))
      (node (ref "C7") (pin "2") (pinfunction "2_2") (pintype "passive"))
      (node (ref "C8") (pin "2") (pinfunction "2_2") (pintype "passive"))
      (node (ref "C9") (pin "2") (pinfunction "2_2") (pintype "passive"))
      (node (ref "CP1202N") (pin "12") (pinfunction "GND_12") (pintype "power_in"))
      (node (ref "CP1202N") (pin "3") (pinfunction "GND_3") (pintype "power_in"))
      (node (ref "D1") (pin "2") (pinfunction "A2_2") (pintype "passive"))
      (node (ref "D18") (pin "3") (pinfunction "3_3") (pintype "bidirectional"))
      (node (ref "D19") (pin "3") (pinfunction "3_3") (pintype "bidirectional"))
      (node (ref "D2") (pin "1") (pinfunction "1_1") (pintype "passive"))
      (node (ref "D22") (pin "A") (pinfunction "A_A") (pintype "passive"))
      (node (ref "D24") (pin "A") (pinfunction "A_A") (pintype "passive"))
      (node (ref "D25") (pin "A") (pinfunction "A_A") (pintype "passive"))
      (node (ref "D31") (pin "C") (pinfunction "C_C") (pintype "passive"))
      (node (ref "D32") (pin "A") (pinfunction "1_A") (pintype "passive"))
      (node (ref "D4") (pin "1") (pinfunction "-_1") (pintype "passive"))
      (node (ref "D5") (pin "1") (pinfunction "-_1") (pintype "passive"))
      (node (ref "D6") (pin "1") (pinfunction "-_1") (pintype "passive"))
      (node (ref "D7") (pin "A") (pinfunction "A_A") (pintype "passive"))
      (node (ref "IC2") (pin "10") (pinfunction "-IN_10") (pintype "input"))
      (node (ref "IC2") (pin "11") (pinfunction "+IN_11") (pintype "input"))
      (node (ref "IC2") (pin "12") (pinfunction "GND_12") (pintype "power_in"))
      (node (ref "IC2") (pin "13") (pinfunction "OUT_13") (pintype "open_collector"))
      (node (ref "J2") (pin "6") (pinfunction "6_6") (pintype "passive"))
      (node (ref "J3") (pin "GND") (pinfunction "GND_GND") (pintype "power_in"))
      (node (ref "J3") (pin "SHLD1") (pinfunction "SHIELD_SHLD1") (pintype "bidirectional"))
      (node (ref "J3") (pin "SHLD2") (pinfunction "SHIELD_SHLD2") (pintype "bidirectional"))
      (node (ref "J5") (pin "14") (pinfunction "14_14") (pintype "passive"))
      (node (ref "J6") (pin "1") (pinfunction "1_1") (pintype "passive"))
      (node (ref "J6") (pin "13") (pinfunction "13_13") (pintype "passive"))
      (node (ref "R21") (pin "2") (pinfunction "2_2") (pintype "passive"))
      (node (ref "R25") (pin "1") (pinfunction "1_1") (pintype "passive"))
      (node (ref "R31") (pin "1") (pinfunction "1_1") (pintype "passive"))
      (node (ref "R37") (pin "1") (pinfunction "1_1") (pintype "passive"))
      (node (ref "R38") (pin "1") (pinfunction "1_1") (pintype "passive"))
      (node (ref "R41") (pin "1") (pinfunction "1_1") (pintype "passive"))
      (node (ref "S1") (pin "1") (pinfunction "1_1") (pintype "passive"))
      (node (ref "S2") (pin "1") (pinfunction "1_1") (pintype "passive"))
      (node (ref "T1") (pin "2") (pinfunction "S_2") (pintype "passive"))
      (node (ref "T2") (pin "2") (pinfunction "S_2") (pintype "passive"))
      (node (ref "T3") (pin "2") (pinfunction "S_2") (pintype "passive"))
      (node (ref "T6") (pin "2") (pinfunction "S_2") (pintype "passive"))
      (node (ref "T7") (pin "E") (pinfunction "E_E") (pintype "passive"))
      (node (ref "T8") (pin "E") (pinfunction "E_E") (pintype "passive"))
      (node (ref "U1") (pin "2") (pinfunction "GNDA_2") (pintype "power_in"))
      (node (ref "U1") (pin "5") (pinfunction "GNDB_5") (pintype "power_in"))
      (node (ref "U10") (pin "8") (pinfunction "GND_8") (pintype "power_in"))
      (node (ref "U15") (pin "1") (pinfunction "GND_1") (pintype "input"))
      (node (ref "U16") (pin "13") (pinfunction "GND_13") (pintype "power_in"))
      (node (ref "U16") (pin "2") (pinfunction "GND_2") (pintype "power_in"))
      (node (ref "U19") (pin "1") (pinfunction "GND_1") (pintype "input"))
    )
    (net (code "6") (name "HS_CAN_H") (class "Default")
      (node (ref "D18") (pin "2") (pinfunction "2_2") (pintype "bidirectional"))
      (node (ref "J2") (pin "4") (pinfunction "4_4") (pintype "passive"))
      (node (ref "R20") (pin "2") (pinfunction "2_2") (pintype "passive"))
      (node (ref "U1") (pin "10") (pinfunction "CANH2_10") (pintype "input"))
    )
    (net (code "7") (name "HS_CAN_L") (class "Default")
      (node (ref "D18") (pin "1") (pinfunction "1_1") (pintype "bidirectional"))
      (node (ref "J2") (pin "5") (pinfunction "5_5") (pintype "passive"))
      (node (ref "R19") (pin "2") (pinfunction "2_2") (pintype "passive"))
      (node (ref "U1") (pin "9") (pinfunction "CANL2_9") (pintype "input"))
    )
    (net (code "8") (name "HS_CAN_RX") (class "Default")
      (node (ref "J5") (pin "4") (pinfunction "4_4") (pintype "passive"))
      (node (ref "U1") (pin "7") (pinfunction "RXD2_7") (pintype "input"))
    )
    (net (code "9") (name "HS_CAN_TX") (class "Default")
      (node (ref "J5") (pin "5") (pinfunction "5_5") (pintype "passive"))
      (node (ref "R45") (pin "1") (pinfunction "1_1") (pintype "passive"))
      (node (ref "U1") (pin "6") (pinfunction "TXD2_6") (pintype "output"))
    )
    (net (code "10") (name "J1850_BUS+") (class "Default")
      (node (ref "D25") (pin "C") (pinfunction "C_C") (pintype "passive"))
      (node (ref "D28") (pin "C") (pinfunction "C_C") (pintype "passive"))
      (node (ref "IC2") (pin "7") (pinfunction "+IN_7") (pintype "input"))
      (node (ref "J2") (pin "9") (pinfunction "9_9") (pintype "passive"))
      (node (ref "R22") (pin "2") (pinfunction "2_2") (pintype "passive"))
      (node (ref "R23") (pin "1") (pinfunction "1_1") (pintype "passive"))
      (node (ref "R23") (pin "2") (pinfunction "2_2") (pintype "passive"))
      (node (ref "R29") (pin "1") (pinfunction "1_1") (pintype "passive"))
    )
    (net (code "11") (name "J1850_BUS+_TX") (class "Default")
      (node (ref "J6") (pin "10") (pinfunction "10_10") (pintype "passive"))
      (node (ref "R37") (pin "2") (pinfunction "2_2") (pintype "passive"))
      (node (ref "T6") (pin "1") (pinfunction "G_1") (pintype "passive"))
    )
    (net (code "12") (name "J1850_BUS-") (class "Default")
      (node (ref "D24") (pin "C") (pinfunction "C_C") (pintype "passive"))
      (node (ref "IC2") (pin "6") (pinfunction "-IN_6") (pintype "input"))
      (node (ref "J2") (pin "10") (pinfunction "10_10") (pintype "passive"))
      (node (ref "R36") (pin "1") (pinfunction "1_1") (pintype "passive"))
      (node (ref "R7") (pin "1") (pinfunction "1_1") (pintype "passive"))
      (node (ref "R7") (pin "2") (pinfunction "2_2") (pintype "passive"))
      (node (ref "T2") (pin "3") (pinfunction "D_3") (pintype "passive"))
    )
    (net (code "13") (name "K_LINE") (class "Default")
      (node (ref "J2") (pin "7") (pinfunction "7_7") (pintype "passive"))
      (node (ref "R34") (pin "1") (pinfunction "1_1") (pintype "passive"))
      (node (ref "R42") (pin "1") (pinfunction "1_1") (pintype "passive"))
      (node (ref "T7") (pin "C") (pinfunction "C_C") (pintype "passive"))
    )
    (net (code "14") (name "L_LINE") (class "Default")
      (node (ref "J2") (pin "8") (pinfunction "8_8") (pintype "passive"))
      (node (ref "R33") (pin "1") (pinfunction "1_1") (pintype "passive"))
      (node (ref "T8") (pin "C") (pinfunction "C_C") (pintype "passive"))
    )
    (net (code "15") (name "MS_CAN_H") (class "Default")
      (node (ref "D19") (pin "2") (pinfunction "2_2") (pintype "bidirectional"))
      (node (ref "J2") (pin "2") (pinfunction "2_2") (pintype "passive"))
      (node (ref "R18") (pin "2") (pinfunction "2_2") (pintype "passive"))
      (node (ref "U1") (pin "13") (pinfunction "CANH1_13") (pintype "input"))
    )
    (net (code "16") (name "MS_CAN_L") (class "Default")
      (node (ref "D19") (pin "1") (pinfunction "1_1") (pintype "bidirectional"))
      (node (ref "J2") (pin "3") (pinfunction "3_3") (pintype "passive"))
      (node (ref "R17") (pin "2") (pinfunction "2_2") (pintype "passive"))
      (node (ref "U1") (pin "12") (pinfunction "CANL1_12") (pintype "input"))
    )
    (net (code "17") (name "MS_CAN_RX") (class "Default")
      (node (ref "J5") (pin "6") (pinfunction "6_6") (pintype "passive"))
      (node (ref "U1") (pin "4") (pinfunction "RXD1_4") (pintype "input"))
    )
    (net (code "18") (name "MS_CAN_TX") (class "Default")
      (node (ref "J5") (pin "7") (pinfunction "7_7") (pintype "passive"))
      (node (ref "R24") (pin "1") (pinfunction "1_1") (pintype "passive"))
      (node (ref "U1") (pin "1") (pinfunction "TXD1_1") (pintype "output"))
    )
    (net (code "19") (name "Net-(C11-Pad1)") (class "Default")
      (node (ref "C11") (pin "1") (pinfunction "1_1") (pintype "passive"))
      (node (ref "R17") (pin "1") (pinfunction "1_1") (pintype "passive"))
    )
    (net (code "20") (name "Net-(C20-Pad1)") (class "Default")
      (node (ref "C20") (pin "1") (pinfunction "1_1") (pintype "passive"))
      (node (ref "R18") (pin "1") (pinfunction "1_1") (pintype "passive"))
    )
    (net (code "21") (name "Net-(C22-Pad1)") (class "Default")
      (node (ref "C22") (pin "1") (pinfunction "1_1") (pintype "passive"))
      (node (ref "R19") (pin "1") (pinfunction "1_1") (pintype "passive"))
    )
    (net (code "22") (name "Net-(C23-Pad1)") (class "Default")
      (node (ref "C23") (pin "1") (pinfunction "1_1") (pintype "passive"))
      (node (ref "R20") (pin "1") (pinfunction "1_1") (pintype "passive"))
    )
    (net (code "23") (name "Net-(CP1202N-D+)") (class "Default")
      (node (ref "CP1202N") (pin "4") (pinfunction "D+_4") (pintype "input"))
      (node (ref "D2") (pin "4") (pinfunction "4_4") (pintype "passive"))
      (node (ref "J3") (pin "D+") (pinfunction "D+_D+") (pintype "bidirectional"))
    )
    (net (code "24") (name "Net-(CP1202N-D-)") (class "Default")
      (node (ref "CP1202N") (pin "5") (pinfunction "D-_5") (pintype "input"))
      (node (ref "D2") (pin "3") (pinfunction "3_3") (pintype "passive"))
      (node (ref "J3") (pin "D-") (pinfunction "D-_D-") (pintype "bidirectional"))
    )
    (net (code "25") (name "Net-(CP1202N-GPIO2{slash}TXT)") (class "Default")
      (node (ref "CP1202N") (pin "20") (pinfunction "GPIO2/TXT_20") (pintype "bidirectional"))
      (node (ref "D8") (pin "1") (pinfunction "-_1") (pintype "passive"))
    )
    (net (code "26") (name "Net-(CP1202N-GPIO3{slash}RXT)") (class "Default")
      (node (ref "CP1202N") (pin "19") (pinfunction "GPIO3/RXT_19") (pintype "bidirectional"))
      (node (ref "D9") (pin "1") (pinfunction "-_1") (pintype "passive"))
    )
    (net (code "27") (name "Net-(CP1202N-RSTB)") (class "Default")
      (node (ref "CP1202N") (pin "9") (pinfunction "RSTB_9") (pintype "input"))
      (node (ref "R3") (pin "2") (pinfunction "2_2") (pintype "passive"))
    )
    (net (code "28") (name "Net-(CP1202N-VBUS)") (class "Default")
      (node (ref "C1") (pin "1") (pinfunction "1_1") (pintype "passive"))
      (node (ref "C2") (pin "1") (pinfunction "1_1") (pintype "passive"))
      (node (ref "CP1202N") (pin "7") (pinfunction "VREGIN_7") (pintype "power_in"))
      (node (ref "CP1202N") (pin "8") (pinfunction "VBUS_8") (pintype "input"))
      (node (ref "D2") (pin "2") (pinfunction "2_2") (pintype "passive"))
      (node (ref "J3") (pin "VBUS") (pinfunction "VBUS_VBUS") (pintype "power_in"))
    )
    (net (code "29") (name "Net-(D3--)") (class "Default")
      (node (ref "D3") (pin "1") (pinfunction "-_1") (pintype "passive"))
      (node (ref "R4") (pin "2") (pinfunction "2_2") (pintype "passive"))
    )
    (net (code "30") (name "Net-(D4-+)") (class "Default")
      (node (ref "D4") (pin "2") (pinfunction "+_2") (pintype "passive"))
      (node (ref "R14") (pin "1") (pinfunction "1_1") (pintype "passive"))
    )
    (net (code "31") (name "Net-(D5-+)") (class "Default")
      (node (ref "D5") (pin "2") (pinfunction "+_2") (pintype "passive"))
      (node (ref "R15") (pin "1") (pinfunction "1_1") (pintype "passive"))
    )
    (net (code "32") (name "Net-(D6-+)") (class "Default")
      (node (ref "D6") (pin "2") (pinfunction "+_2") (pintype "passive"))
      (node (ref "R16") (pin "1") (pinfunction "1_1") (pintype "passive"))
    )
    (net (code "33") (name "Net-(D8-+)") (class "Default")
      (node (ref "D8") (pin "2") (pinfunction "+_2") (pintype "passive"))
      (node (ref "R5") (pin "1") (pinfunction "1_1") (pintype "passive"))
    )
    (net (code "34") (name "Net-(D9-+)") (class "Default")
      (node (ref "D9") (pin "2") (pinfunction "+_2") (pintype "passive"))
      (node (ref "R6") (pin "1") (pinfunction "1_1") (pintype "passive"))
    )
    (net (code "35") (name "Net-(D26-PadC)") (class "Default")
      (node (ref "D26") (pin "C") (pinfunction "C_C") (pintype "passive"))
      (node (ref "R36") (pin "2") (pinfunction "2_2") (pintype "passive"))
    )
    (net (code "36") (name "Net-(D31-PadA)") (class "Default")
      (node (ref "D31") (pin "A") (pinfunction "A_A") (pintype "passive"))
      (node (ref "R22") (pin "1") (pinfunction "1_1") (pintype "passive"))
    )
    (net (code "37") (name "Net-(D32-2)") (class "Default")
      (node (ref "D30") (pin "A") (pinfunction "A_A") (pintype "passive"))
      (node (ref "D32") (pin "C") (pinfunction "2_C") (pintype "passive"))
      (node (ref "F5") (pin "2") (pinfunction "2_2") (pintype "bidirectional"))
    )
    (net (code "38") (name "Net-(IC2A-+IN)") (class "Default")
      (node (ref "D22") (pin "C") (pinfunction "C_C") (pintype "passive"))
      (node (ref "IC2") (pin "5") (pinfunction "+IN_5") (pintype "input"))
      (node (ref "R29") (pin "2") (pinfunction "2_2") (pintype "passive"))
    )
    (net (code "39") (name "Net-(IC2A--IN)") (class "Default")
      (node (ref "IC2") (pin "4") (pinfunction "-IN_4") (pintype "input"))
      (node (ref "R25") (pin "2") (pinfunction "2_2") (pintype "passive"))
      (node (ref "R26") (pin "1") (pinfunction "1_1") (pintype "passive"))
    )
    (net (code "40") (name "Net-(IC2C-+IN)") (class "Default")
      (node (ref "IC2") (pin "9") (pinfunction "+IN_9") (pintype "input"))
      (node (ref "R39") (pin "1") (pinfunction "1_1") (pintype "passive"))
      (node (ref "R41") (pin "2") (pinfunction "2_2") (pintype "passive"))
    )
    (net (code "41") (name "Net-(IC2C--IN)") (class "Default")
      (node (ref "D7") (pin "C") (pinfunction "C_C") (pintype "passive"))
      (node (ref "IC2") (pin "8") (pinfunction "-IN_8") (pintype "input"))
      (node (ref "R42") (pin "2") (pinfunction "2_2") (pintype "passive"))
    )
    (net (code "42") (name "Net-(R1-Pad1)") (class "Default")
      (node (ref "R1") (pin "1") (pinfunction "1_1") (pintype "passive"))
      (node (ref "S2") (pin "2") (pinfunction "2_2") (pintype "passive"))
    )
    (net (code "43") (name "Net-(R11-Pad2)") (class "Default")
      (node (ref "R11") (pin "2") (pinfunction "2_2") (pintype "passive"))
      (node (ref "T7") (pin "B") (pinfunction "B_B") (pintype "passive"))
    )
    (net (code "44") (name "Net-(R35-Pad2)") (class "Default")
      (node (ref "R35") (pin "2") (pinfunction "2_2") (pintype "passive"))
      (node (ref "T8") (pin "B") (pinfunction "B_B") (pintype "passive"))
    )
    (net (code "45") (name "Net-(T1-D)") (class "Default")
      (node (ref "R13") (pin "1") (pinfunction "1_1") (pintype "passive"))
      (node (ref "T1") (pin "3") (pinfunction "D_3") (pintype "passive"))
    )
    (net (code "46") (name "Net-(T3-D)") (class "Default")
      (node (ref "R30") (pin "1") (pinfunction "1_1") (pintype "passive"))
      (node (ref "R31") (pin "2") (pinfunction "2_2") (pintype "passive"))
      (node (ref "T3") (pin "3") (pinfunction "D_3") (pintype "passive"))
    )
    (net (code "47") (name "Net-(T6-D)") (class "Default")
      (node (ref "R44") (pin "1") (pinfunction "1_1") (pintype "passive"))
      (node (ref "T6") (pin "3") (pinfunction "D_3") (pintype "passive"))
      (node (ref "T9") (pin "1") (pinfunction "G_1") (pintype "passive"))
    )
    (net (code "48") (name "Net-(T9-D)") (class "Default")
      (node (ref "D28") (pin "A") (pinfunction "A_A") (pintype "passive"))
      (node (ref "T9") (pin "3") (pinfunction "D_3") (pintype "passive"))
    )
    (net (code "49") (name "Net-(U1-STBN1)") (class "Default")
      (node (ref "R8") (pin "1") (pinfunction "1_1") (pintype "passive"))
      (node (ref "U1") (pin "14") (pinfunction "STBN1_14") (pintype "input"))
    )
    (net (code "50") (name "Net-(U1-STBN2)") (class "Default")
      (node (ref "R9") (pin "1") (pinfunction "1_1") (pintype "passive"))
      (node (ref "U1") (pin "8") (pinfunction "STBN2_8") (pintype "input"))
    )
    (net (code "51") (name "Net-(U9-ADJ)") (class "Default")
      (node (ref "R10") (pin "1") (pinfunction "1_1") (pintype "passive"))
      (node (ref "R30") (pin "2") (pinfunction "2_2") (pintype "passive"))
      (node (ref "U9") (pin "1") (pinfunction "ADJ_1") (pintype "input"))
    )
    (net (code "52") (name "Net-(U10-LOAD)") (class "Default")
      (node (ref "R40") (pin "1") (pinfunction "1_1") (pintype "passive"))
      (node (ref "U10") (pin "6") (pinfunction "LOAD_6") (pintype "output"))
    )
    (net (code "53") (name "Net-(U16-P0_2)") (class "Default")
      (node (ref "R4") (pin "1") (pinfunction "1_1") (pintype "passive"))
      (node (ref "U16") (pin "12") (pinfunction "P0_2_12") (pintype "bidirectional"))
    )
    (net (code "54") (name "Net-(U16-P2_0)") (class "Default")
      (node (ref "R1") (pin "2") (pinfunction "2_2") (pintype "passive"))
      (node (ref "U16") (pin "16") (pinfunction "P2_0_16") (pintype "input"))
    )
    (net (code "55") (name "Net-(U16-RST_N)") (class "Default")
      (node (ref "C7") (pin "1") (pinfunction "1_1") (pintype "passive"))
      (node (ref "R2") (pin "1") (pinfunction "1_1") (pintype "passive"))
      (node (ref "S1") (pin "2") (pinfunction "2_2") (pintype "passive"))
      (node (ref "U16") (pin "10") (pinfunction "RST_N_10") (pintype "input"))
    )
    (net (code "56") (name "PWM_RX") (class "Default")
      (node (ref "IC2") (pin "1") (pinfunction "OUT_1") (pintype "open_collector"))
      (node (ref "J6") (pin "9") (pinfunction "9_9") (pintype "passive"))
      (node (ref "R28") (pin "1") (pinfunction "1_1") (pintype "passive"))
    )
    (net (code "57") (name "PWM{slash}~{VPW}") (class "Default")
      (node (ref "J6") (pin "7") (pinfunction "7_7") (pintype "passive"))
      (node (ref "R32") (pin "1") (pinfunction "1_1") (pintype "passive"))
      (node (ref "T3") (pin "1") (pinfunction "G_1") (pintype "passive"))
    )
    (net (code "58") (name "SW_CAN") (class "Default")
      (node (ref "C6") (pin "1") (pinfunction "1_1") (pintype "passive"))
      (node (ref "D1") (pin "1") (pinfunction "A1_1") (pintype "passive"))
      (node (ref "J2") (pin "1") (pinfunction "1_1") (pintype "passive"))
      (node (ref "R13") (pin "2") (pinfunction "2_2") (pintype "passive"))
      (node (ref "R40") (pin "2") (pinfunction "2_2") (pintype "passive"))
      (node (ref "U10") (pin "7") (pinfunction "CANH_7") (pintype "bidirectional"))
    )
    (net (code "59") (name "SW_CAN_LOAD") (class "Default")
      (node (ref "J5") (pin "12") (pinfunction "12_12") (pintype "passive"))
      (node (ref "R21") (pin "1") (pinfunction "1_1") (pintype "passive"))
      (node (ref "T1") (pin "1") (pinfunction "G_1") (pintype "passive"))
    )
    (net (code "60") (name "SW_CAN_MODE0") (class "Default")
      (node (ref "J5") (pin "10") (pinfunction "10_10") (pintype "passive"))
      (node (ref "U10") (pin "2") (pinfunction "MODE0_2") (pintype "input"))
    )
    (net (code "61") (name "SW_CAN_MODE1") (class "Default")
      (node (ref "J5") (pin "11") (pinfunction "11_11") (pintype "passive"))
      (node (ref "U10") (pin "3") (pinfunction "MODE1_3") (pintype "input"))
    )
    (net (code "62") (name "SW_CAN_RX") (class "Default")
      (node (ref "J5") (pin "8") (pinfunction "8_8") (pintype "passive"))
      (node (ref "R12") (pin "1") (pinfunction "1_1") (pintype "passive"))
      (node (ref "U10") (pin "4") (pinfunction "RX_4") (pintype "input"))
    )
    (net (code "63") (name "SW_CAN_TX") (class "Default")
      (node (ref "J5") (pin "9") (pinfunction "9_9") (pintype "passive"))
      (node (ref "R46") (pin "1") (pinfunction "1_1") (pintype "passive"))
      (node (ref "U10") (pin "1") (pinfunction "TX_1") (pintype "input"))
    )
    (net (code "64") (name "UART_RX") (class "Default")
      (node (ref "CP1202N") (pin "18") (pinfunction "TXD_18") (pintype "output"))
      (node (ref "J5") (pin "1") (pinfunction "1_1") (pintype "passive"))
      (node (ref "U16") (pin "8") (pinfunction "HCI_TXD_8") (pintype "output"))
    )
    (net (code "65") (name "UART_TX") (class "Default")
      (node (ref "CP1202N") (pin "17") (pinfunction "RXD_17") (pintype "input"))
      (node (ref "J5") (pin "2") (pinfunction "2_2") (pintype "passive"))
      (node (ref "U16") (pin "7") (pinfunction "HCI_RXD_7") (pintype "input"))
    )
    (net (code "66") (name "VDD_CP") (class "Default")
      (node (ref "C3") (pin "1") (pinfunction "1_1") (pintype "passive"))
      (node (ref "C4") (pin "1") (pinfunction "1_1") (pintype "passive"))
      (node (ref "CP1202N") (pin "6") (pinfunction "VDD_6") (pintype "power_in"))
      (node (ref "R3") (pin "1") (pinfunction "1_1") (pintype "passive"))
      (node (ref "R5") (pin "2") (pinfunction "2_2") (pintype "passive"))
      (node (ref "R6") (pin "2") (pinfunction "2_2") (pintype "passive"))
    )
    (net (code "67") (name "VPW_RX") (class "Default")
      (node (ref "IC2") (pin "2") (pinfunction "OUT_2") (pintype "open_collector"))
      (node (ref "J6") (pin "8") (pinfunction "8_8") (pintype "passive"))
      (node (ref "R27") (pin "1") (pinfunction "1_1") (pintype "passive"))
    )
    (net (code "68") (name "V_J1850") (class "Default")
      (node (ref "R10") (pin "2") (pinfunction "2_2") (pintype "passive"))
      (node (ref "R44") (pin "2") (pinfunction "2_2") (pintype "passive"))
      (node (ref "T9") (pin "2") (pinfunction "S_2") (pintype "passive"))
      (node (ref "U9") (pin "2") (pinfunction "OUT_2") (pintype "output"))
      (node (ref "U9") (pin "4") (pinfunction "OUT_4") (pintype "output"))
    )
    (net (code "69") (name "unconnected-(CP1202N-GPIO0{slash}CLK-Pad2)") (class "Default")
      (node (ref "CP1202N") (pin "2") (pinfunction "GPIO0/CLK_2") (pintype "bidirectional"))
    )
    (net (code "70") (name "unconnected-(CP1202N-GPIO1{slash}RS485-Pad1)") (class "Default")
      (node (ref "CP1202N") (pin "1") (pinfunction "GPIO1/RS485_1") (pintype "bidirectional"))
    )
    (net (code "71") (name "unconnected-(CP1202N-NC-Pad10)") (class "Default")
      (node (ref "CP1202N") (pin "10") (pinfunction "NC_10") (pintype "bidirectional"))
    )
    (net (code "72") (name "unconnected-(CP1202N-RTS-Pad16)") (class "Default")
      (node (ref "CP1202N") (pin "16") (pinfunction "RTS_16") (pintype "output"))
    )
    (net (code "73") (name "unconnected-(CP1202N-SUSPEND-Pad14)") (class "Default")
      (node (ref "CP1202N") (pin "14") (pinfunction "SUSPEND_14") (pintype "output"))
    )
    (net (code "74") (name "unconnected-(CP1202N-SUSPENDB-Pad11)") (class "Default")
      (node (ref "CP1202N") (pin "11") (pinfunction "SUSPENDB_11") (pintype "output"))
    )
    (net (code "75") (name "unconnected-(CP1202N-WAKEUP-Pad13)") (class "Default")
      (node (ref "CP1202N") (pin "13") (pinfunction "WAKEUP_13") (pintype "input"))
    )
    (net (code "76") (name "unconnected-(D1-C-Pad3)") (class "Default")
      (node (ref "D1") (pin "3") (pinfunction "C_3") (pintype "passive"))
    )
    (net (code "77") (name "unconnected-(J6-Pad2)") (class "Default")
      (node (ref "J6") (pin "2") (pinfunction "2_2") (pintype "passive"))
    )
    (net (code "78") (name "unconnected-(J6-Pad12)") (class "Default")
      (node (ref "J6") (pin "12") (pinfunction "12_12") (pintype "passive"))
    )
    (net (code "79") (name "unconnected-(U16-BT_RF-Pad1)") (class "Default")
      (node (ref "U16") (pin "1") (pinfunction "BT_RF_1") (pintype "bidirectional"))
    )
    (net (code "80") (name "unconnected-(U16-P0_0-Pad11)") (class "Default")
      (node (ref "U16") (pin "11") (pinfunction "P0_0_11") (pintype "bidirectional"))
    )
    (net (code "81") (name "unconnected-(U16-P1_2-Pad3)") (class "Default")
      (node (ref "U16") (pin "3") (pinfunction "P1_2_3") (pintype "bidirectional"))
    )
    (net (code "82") (name "unconnected-(U16-P1_3-Pad4)") (class "Default")
      (node (ref "U16") (pin "4") (pinfunction "P1_3_4") (pintype "bidirectional"))
    )
    (net (code "83") (name "unconnected-(U16-P1_6-Pad6)") (class "Default")
      (node (ref "U16") (pin "6") (pinfunction "P1_6_6") (pintype "bidirectional"))
    )
    (net (code "84") (name "unconnected-(U16-P1_7-Pad5)") (class "Default")
      (node (ref "U16") (pin "5") (pinfunction "P1_7_5") (pintype "bidirectional"))
    )
    (net (code "85") (name "unconnected-(U16-P2_7-Pad15)") (class "Default")
      (node (ref "U16") (pin "15") (pinfunction "P2_7_15") (pintype "bidirectional"))
    )
    (net (code "86") (name "unconnected-(U16-P3_6-Pad9)") (class "Default")
      (node (ref "U16") (pin "9") (pinfunction "P3_6_9") (pintype "bidirectional"))
    )
    (net (code "87") (name "~{ISO_K_TX}") (class "Default")
      (node (ref "J6") (pin "4") (pinfunction "4_4") (pintype "passive"))
      (node (ref "R11") (pin "1") (pinfunction "1_1") (pintype "passive"))
    )
    (net (code "88") (name "~{ISO_L_TX}") (class "Default")
      (node (ref "J6") (pin "5") (pinfunction "5_5") (pintype "passive"))
      (node (ref "R35") (pin "1") (pinfunction "1_1") (pintype "passive"))
    )
    (net (code "89") (name "~{ISO_RX}") (class "Default")
      (node (ref "IC2") (pin "14") (pinfunction "OUT_14") (pintype "open_collector"))
      (node (ref "J6") (pin "3") (pinfunction "3_3") (pintype "passive"))
      (node (ref "R43") (pin "1") (pinfunction "1_1") (pintype "passive"))
    )
    (net (code "90") (name "~{J1850_BUS-_TX}") (class "Default")
      (node (ref "J6") (pin "11") (pinfunction "11_11") (pintype "passive"))
      (node (ref "R38") (pin "2") (pinfunction "2_2") (pintype "passive"))
      (node (ref "T2") (pin "1") (pinfunction "G_1") (pintype "passive"))
    )
    (net (code "91") (name "~{UART_CTS}") (class "Default")
      (node (ref "CP1202N") (pin "15") (pinfunction "CTS_15") (pintype "input"))
      (node (ref "J5") (pin "3") (pinfunction "3_3") (pintype "passive"))
    )
  )
)
